# DAC_STM32_Board_v6_-_AD5391.net
KiCad netlist of a schematic drawn in EAGLE
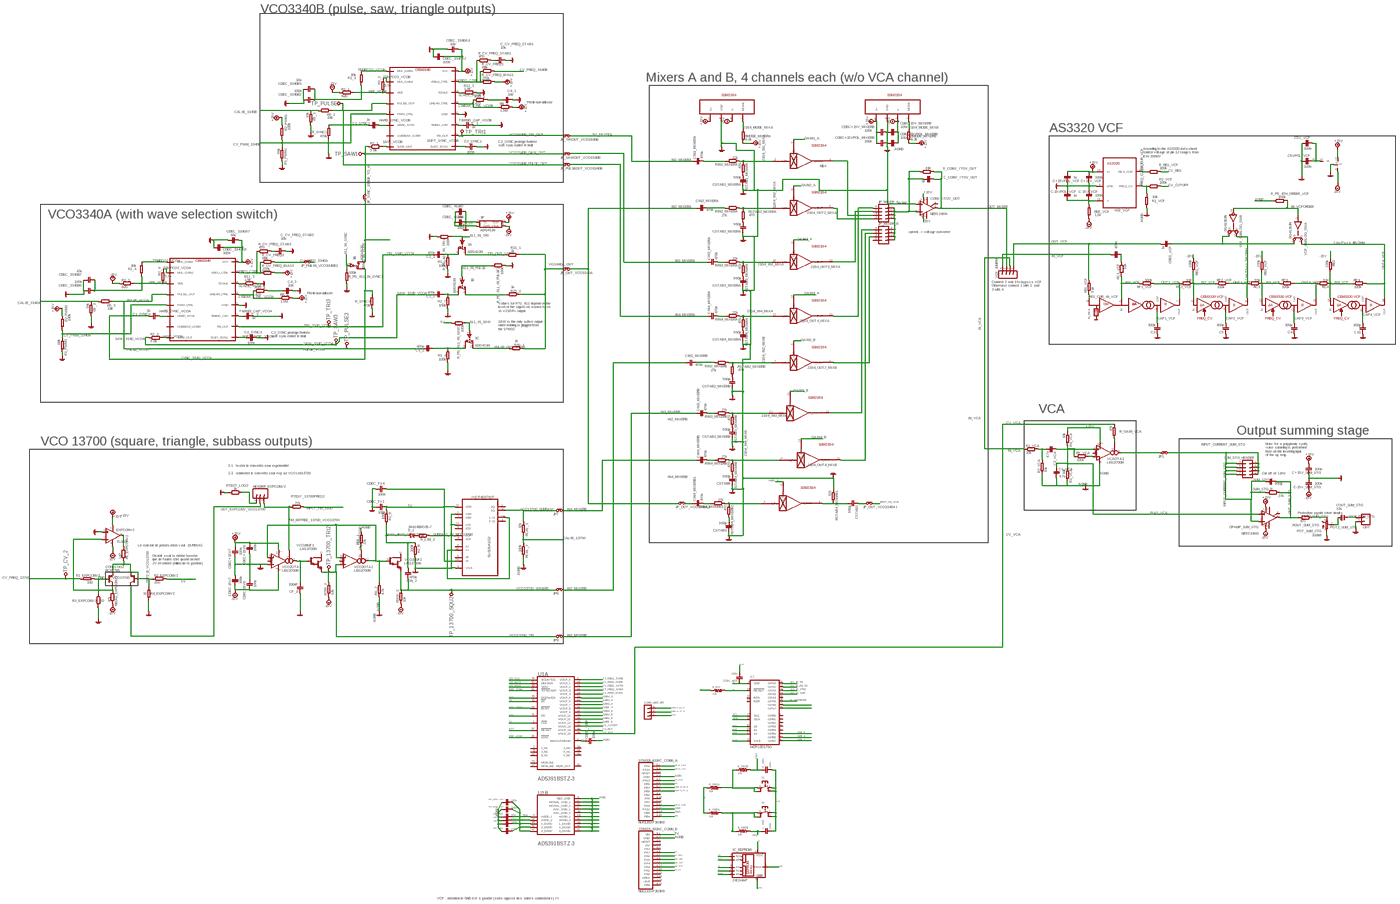
[diagram p0: schematic, sheet 1, overview]
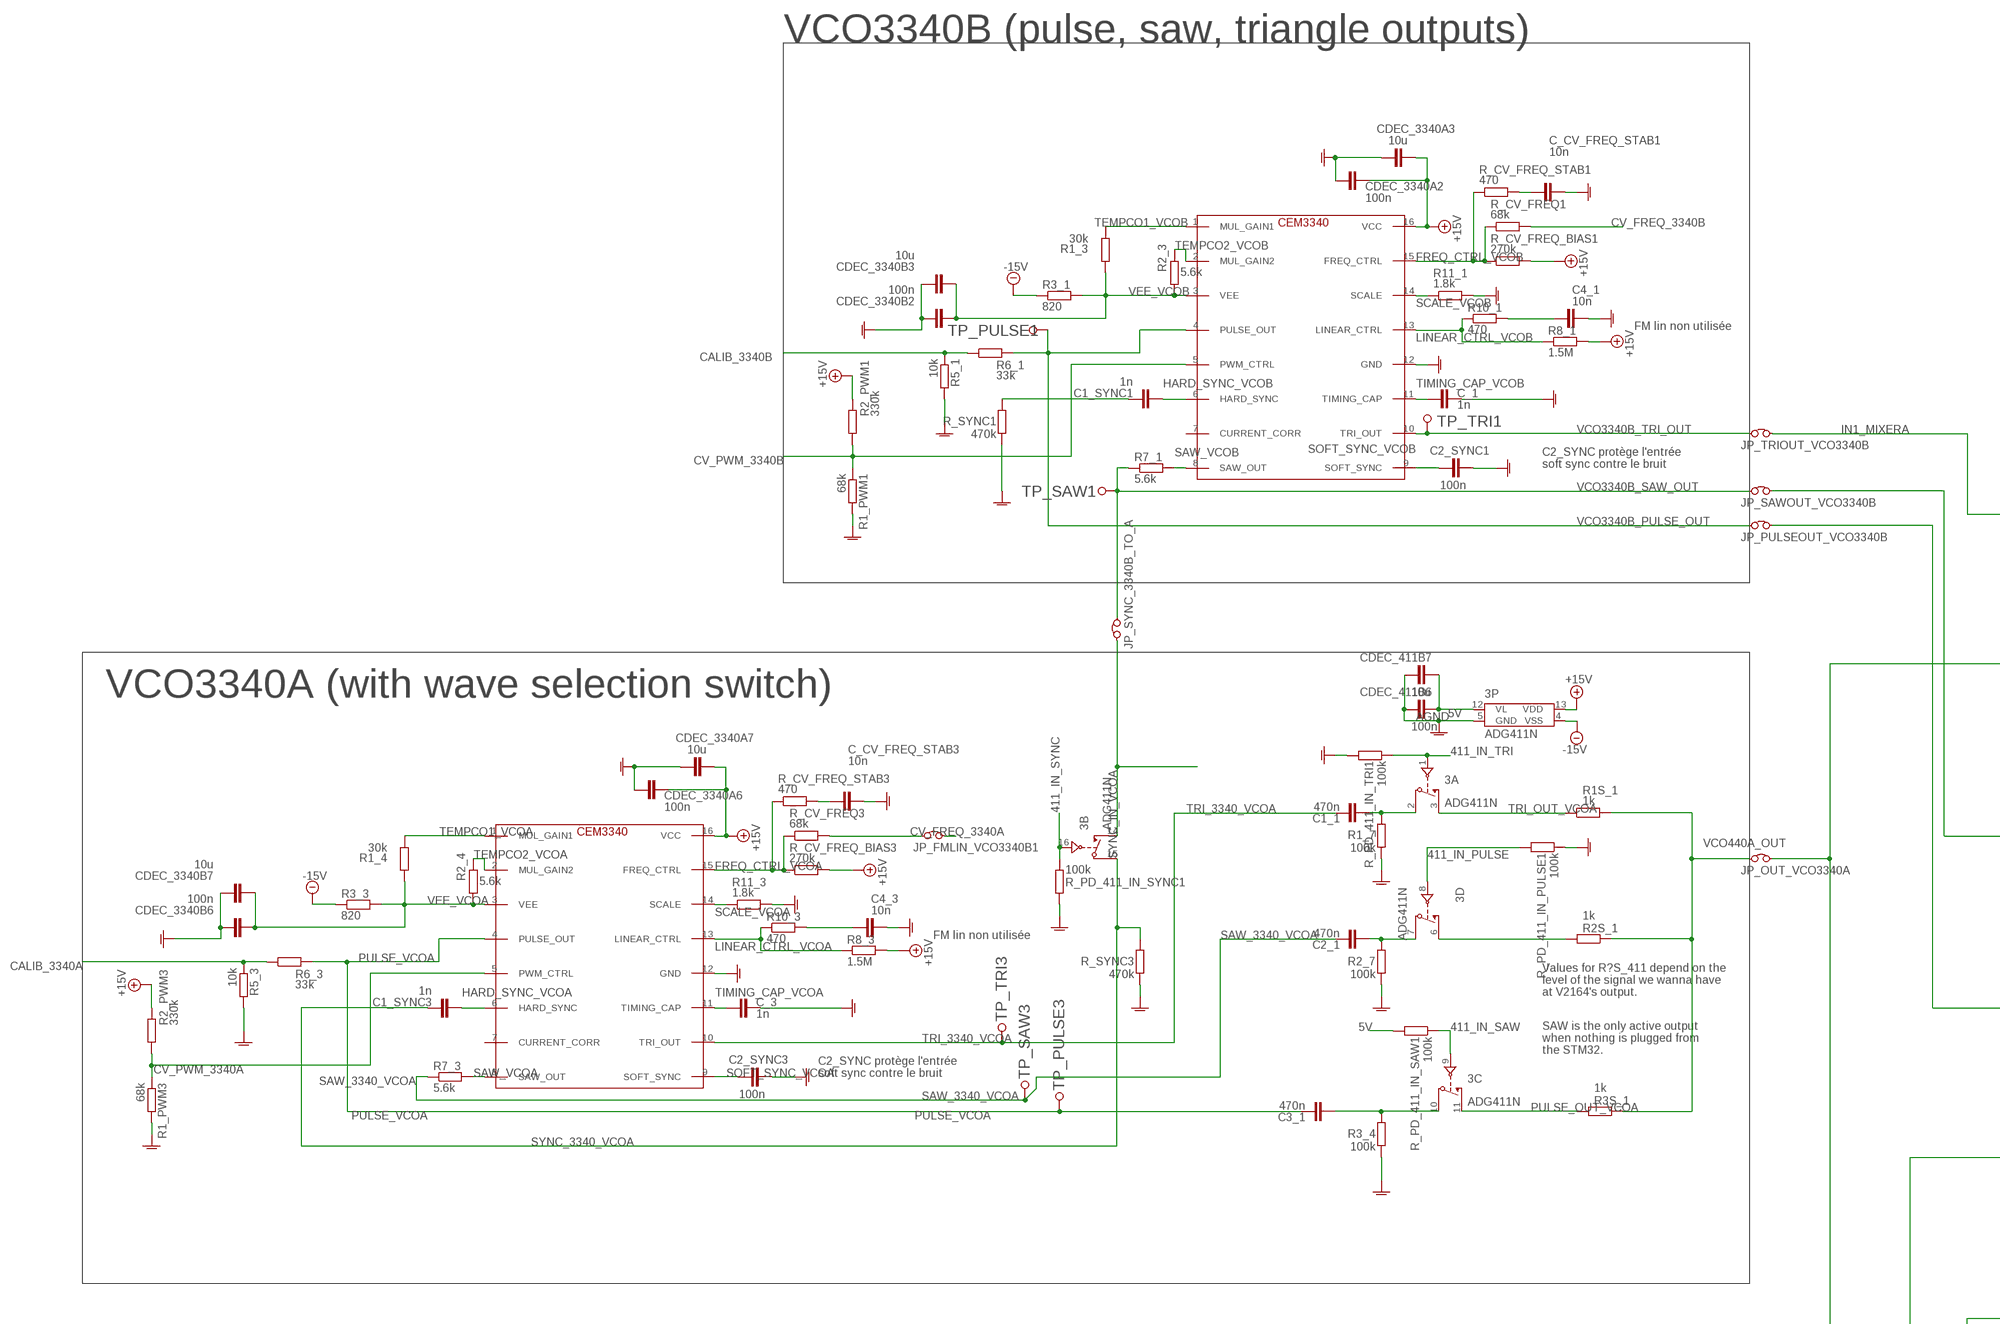
[diagram p1: schematic, sheet 1, part 1 of 5]
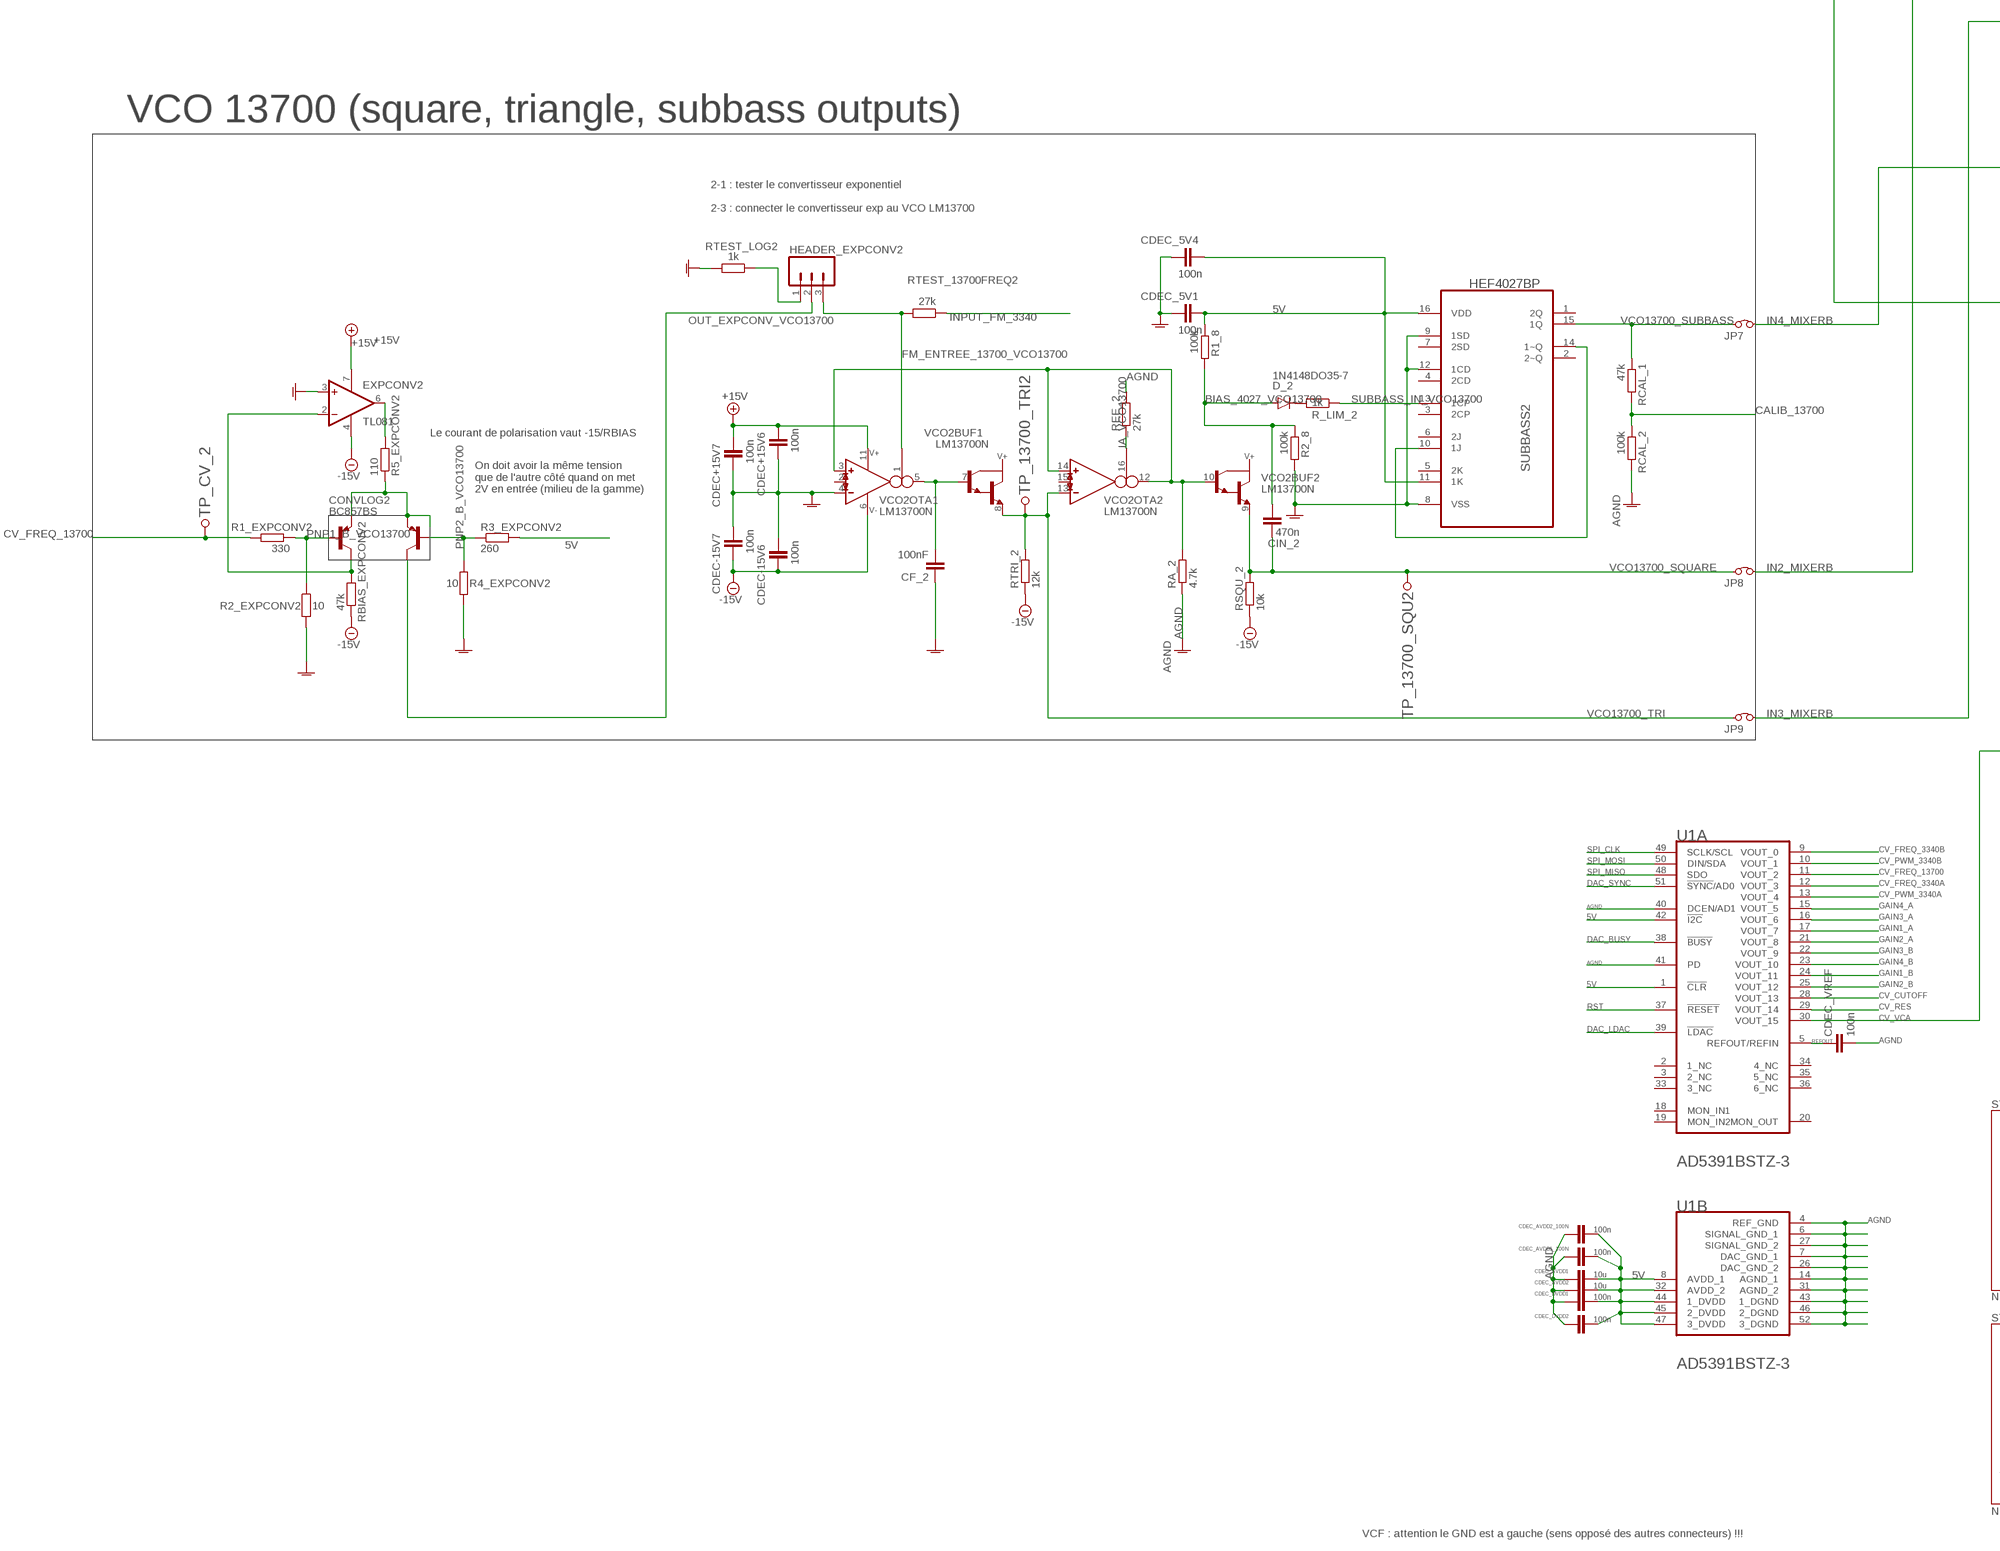
[diagram p2: schematic, sheet 1, part 2 of 5]
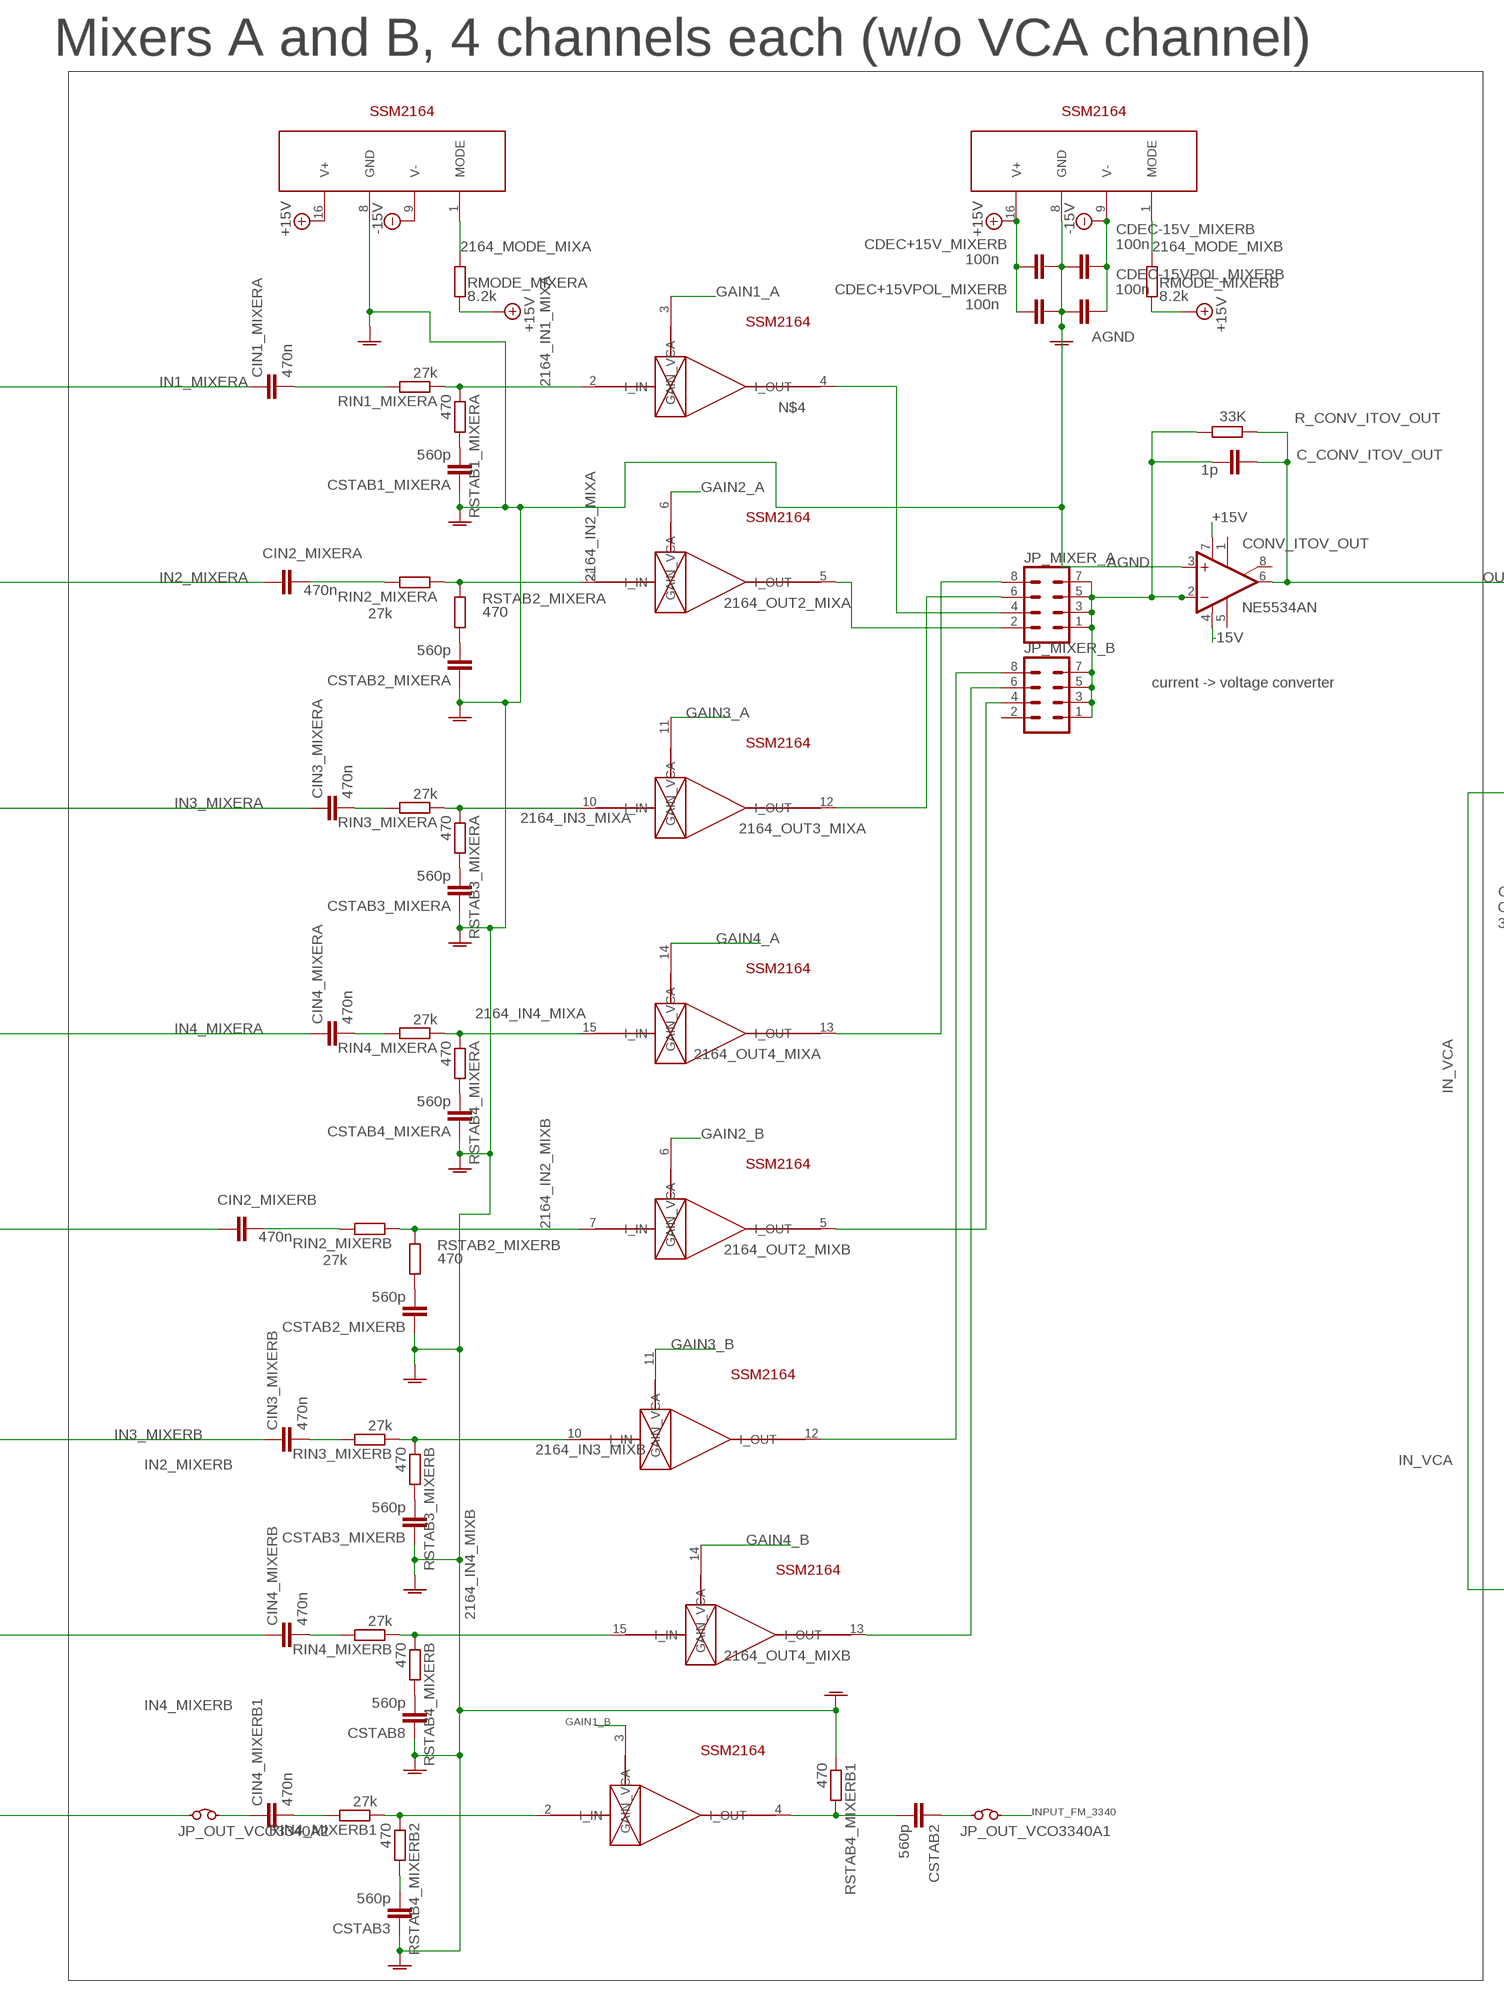
[diagram p3: schematic, sheet 1, part 3 of 5]
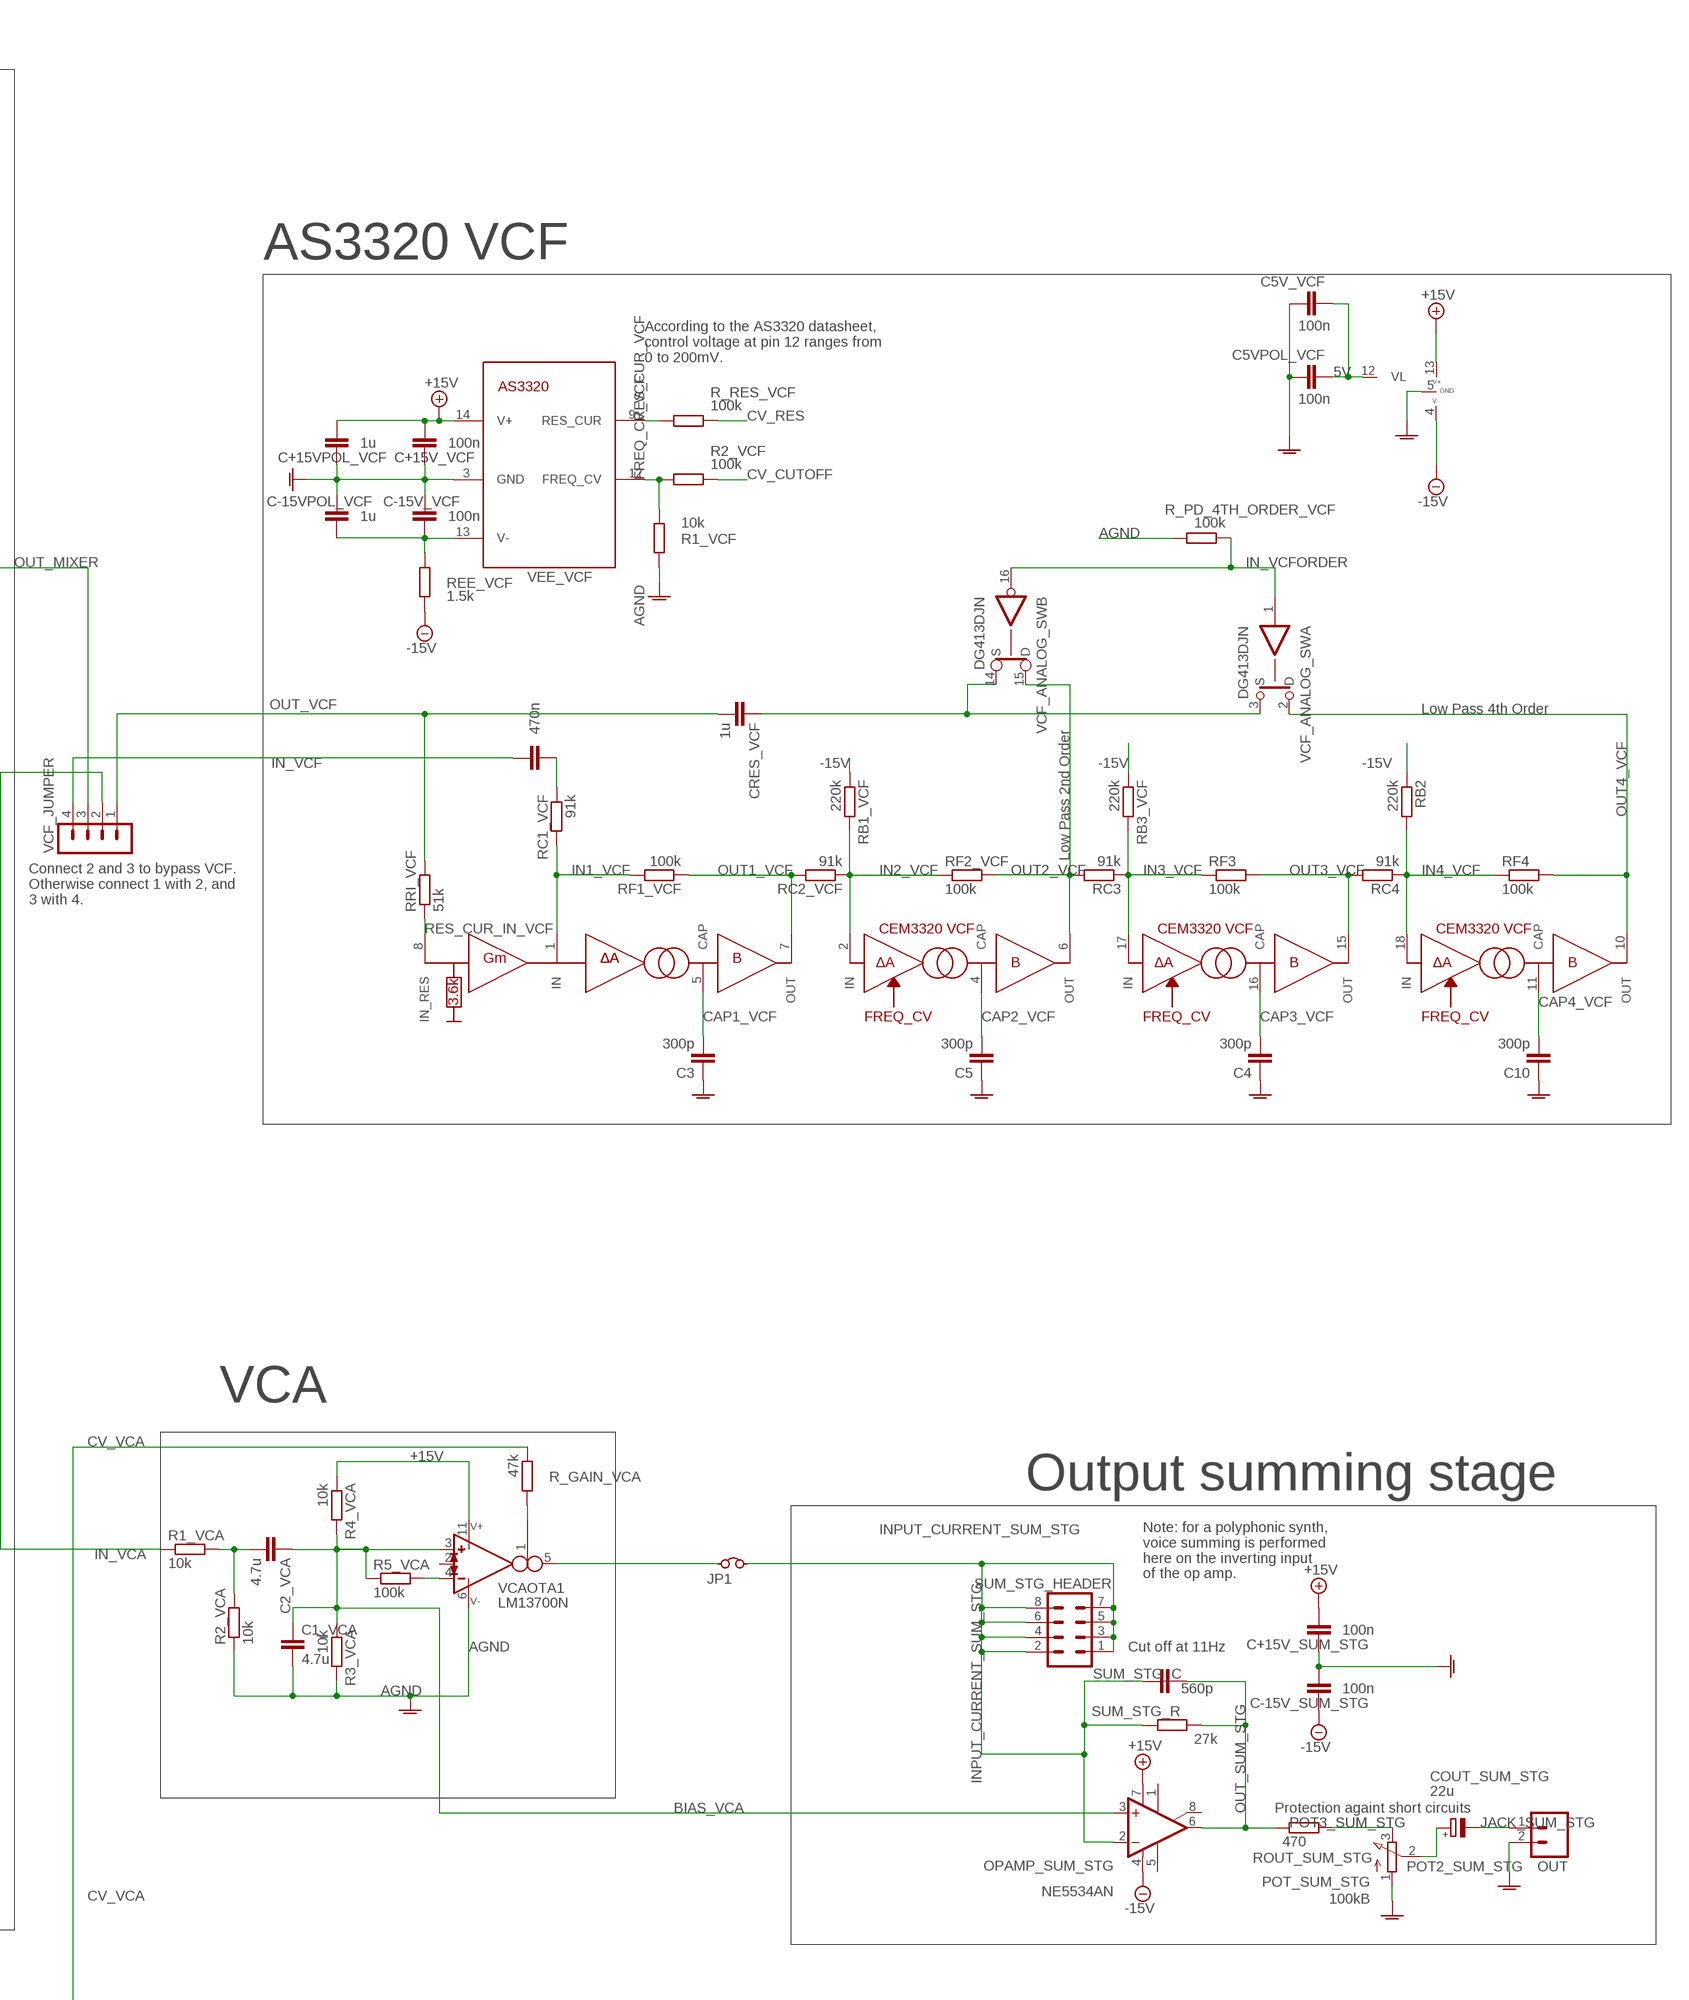
[diagram p4: schematic, sheet 1, part 4 of 5]
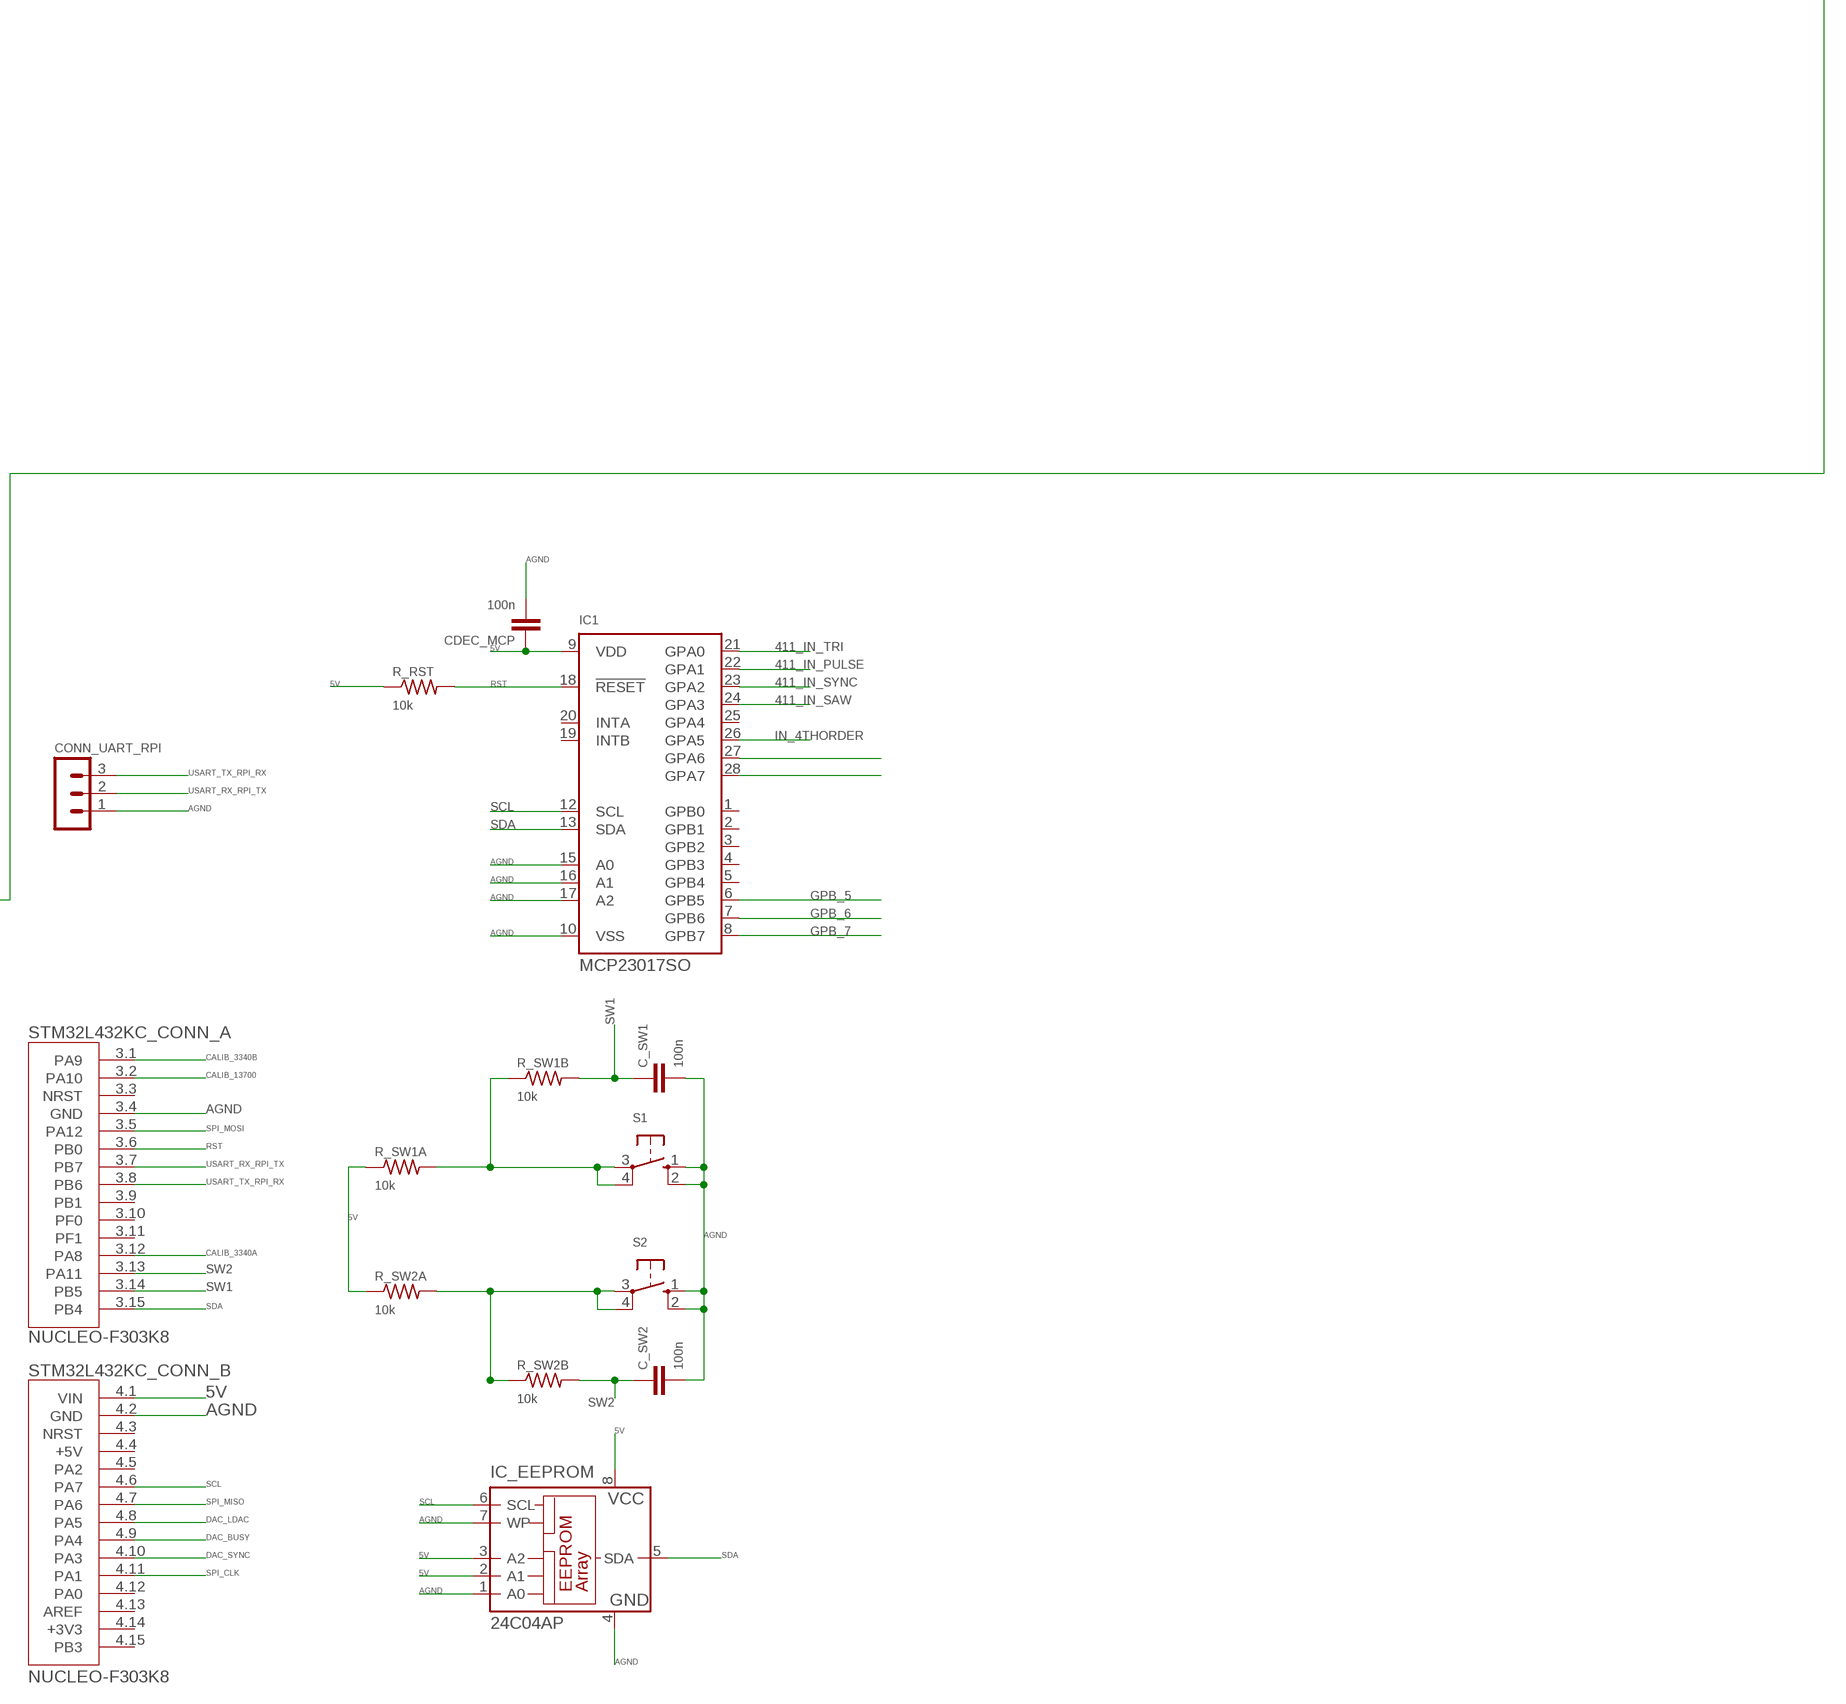
[diagram p5: schematic, sheet 1, part 5 of 5]

(export (version "E")
  (design (tool "Eeschema 10.0.6"))
  (components
    (comp (ref "3")
      (value "ADG411N")
      (footprint "eagle-import:DIL16")
      (fields (field (name "MF") "ALTERA CORPORATION") (field (name "MPN") "ADG411BN"))
      (libsource (lib "eagle-import") (part "ADG411N"))
    )
    (comp (ref "3340A")
      (value "CEM3340")
      (footprint "eagle-import:DIL16")
      (libsource (lib "eagle-import") (part "CEM3340"))
    )
    (comp (ref "3340B")
      (value "CEM3340")
      (footprint "eagle-import:DIL16")
      (libsource (lib "eagle-import") (part "CEM3340"))
    )
    (comp (ref "C+15VPOL_VCF")
      (value "1u")
      (footprint "eagle-import:C075-032X103")
      (libsource (lib "eagle-import") (part "rcl_334_C-EU075-032X103"))
    )
    (comp (ref "C+15V_SUM_STG")
      (value "100n")
      (footprint "eagle-import:C075-032X103")
      (libsource (lib "eagle-import") (part "rcl_334_C-EU075-032X103"))
    )
    (comp (ref "C+15V_VCF")
      (value "100n")
      (footprint "eagle-import:C075-032X103")
      (libsource (lib "eagle-import") (part "rcl_334_C-EU075-032X103"))
    )
    (comp (ref "C-15VPOL_VCF")
      (value "1u")
      (footprint "eagle-import:C075-032X103")
      (libsource (lib "eagle-import") (part "rcl_334_C-EU075-032X103"))
    )
    (comp (ref "C-15V_SUM_STG")
      (value "100n")
      (footprint "eagle-import:C075-032X103")
      (libsource (lib "eagle-import") (part "rcl_334_C-EU075-032X103"))
    )
    (comp (ref "C-15V_VCF")
      (value "100n")
      (footprint "eagle-import:C075-032X103")
      (libsource (lib "eagle-import") (part "rcl_334_C-EU075-032X103"))
    )
    (comp (ref "C1_1")
      (value "470n")
      (footprint "eagle-import:C075-032X103")
      (libsource (lib "eagle-import") (part "rcl_334_C-EU075-032X103"))
    )
    (comp (ref "C1_SYNC1")
      (value "1n")
      (footprint "eagle-import:C075-032X103")
      (libsource (lib "eagle-import") (part "rcl_334_C-EU075-032X103"))
    )
    (comp (ref "C1_SYNC3")
      (value "1n")
      (footprint "eagle-import:C075-032X103")
      (libsource (lib "eagle-import") (part "rcl_334_C-EU075-032X103"))
    )
    (comp (ref "C1_VCA")
      (value "4.7u")
      (footprint "eagle-import:C050-030X075")
      (libsource (lib "eagle-import") (part "rcl_334_C-EU050-030X075"))
    )
    (comp (ref "C2_1")
      (value "470n")
      (footprint "eagle-import:C075-032X103")
      (libsource (lib "eagle-import") (part "rcl_334_C-EU075-032X103"))
    )
    (comp (ref "C2_SYNC1")
      (value "100n")
      (footprint "eagle-import:C075-032X103")
      (libsource (lib "eagle-import") (part "rcl_334_C-EU075-032X103"))
    )
    (comp (ref "C2_SYNC3")
      (value "100n")
      (footprint "eagle-import:C050-025X075")
      (libsource (lib "eagle-import") (part "rcl_334_C-EU050-025X075"))
    )
    (comp (ref "C2_VCA")
      (value "4.7u")
      (footprint "eagle-import:C050-030X075")
      (libsource (lib "eagle-import") (part "rcl_334_C-EU050-030X075"))
    )
    (comp (ref "C3")
      (value "300p")
      (footprint "eagle-import:C075-032X103")
      (libsource (lib "eagle-import") (part "rcl_334_C-EU075-032X103"))
    )
    (comp (ref "C3_1")
      (value "470n")
      (footprint "eagle-import:C102-043X133")
      (libsource (lib "eagle-import") (part "rcl_334_C-EU102-043X133"))
    )
    (comp (ref "C4")
      (value "300p")
      (footprint "eagle-import:C075-032X103")
      (libsource (lib "eagle-import") (part "rcl_334_C-EU075-032X103"))
    )
    (comp (ref "C4_1")
      (value "10n")
      (footprint "eagle-import:C050-025X075")
      (libsource (lib "eagle-import") (part "rcl_334_C-EU050-025X075"))
    )
    (comp (ref "C4_3")
      (value "10n")
      (footprint "eagle-import:C050-025X075")
      (libsource (lib "eagle-import") (part "rcl_334_C-EU050-025X075"))
    )
    (comp (ref "C5")
      (value "300p")
      (footprint "eagle-import:C075-032X103")
      (libsource (lib "eagle-import") (part "rcl_334_C-EU075-032X103"))
    )
    (comp (ref "C5VPOL_VCF")
      (value "100n")
      (footprint "eagle-import:C075-032X103")
      (libsource (lib "eagle-import") (part "rcl_334_C-EU075-032X103"))
    )
    (comp (ref "C5V_VCF")
      (value "100n")
      (footprint "eagle-import:C075-032X103")
      (libsource (lib "eagle-import") (part "rcl_334_C-EU075-032X103"))
    )
    (comp (ref "C10")
      (value "300p")
      (footprint "eagle-import:C075-032X103")
      (libsource (lib "eagle-import") (part "rcl_334_C-EU075-032X103"))
    )
    (comp (ref "CDEC+15V6")
      (value "100n")
      (footprint "eagle-import:C075-032X103")
      (libsource (lib "eagle-import") (part "rcl_334_C-EU075-032X103"))
    )
    (comp (ref "CDEC+15V7")
      (value "100n")
      (footprint "eagle-import:C050-025X075")
      (libsource (lib "eagle-import") (part "rcl_334_C-EU050-025X075"))
    )
    (comp (ref "CDEC+15VPOL_MIXERB")
      (value "100n")
      (footprint "eagle-import:C075-032X103")
      (libsource (lib "eagle-import") (part "rcl_334_C-EU075-032X103"))
    )
    (comp (ref "CDEC+15V_MIXERB")
      (value "100n")
      (footprint "eagle-import:C050-030X075")
      (libsource (lib "eagle-import") (part "rcl_334_C-EU050-030X075"))
    )
    (comp (ref "CDEC-15V6")
      (value "100n")
      (footprint "eagle-import:C050-025X075")
      (libsource (lib "eagle-import") (part "rcl_334_C-EU050-025X075"))
    )
    (comp (ref "CDEC-15V7")
      (value "100n")
      (footprint "eagle-import:C075-032X103")
      (libsource (lib "eagle-import") (part "rcl_334_C-EU075-032X103"))
    )
    (comp (ref "CDEC-15VPOL_MIXERB")
      (value "100n")
      (footprint "eagle-import:C050-030X075")
      (libsource (lib "eagle-import") (part "rcl_334_C-EU050-030X075"))
    )
    (comp (ref "CDEC-15V_MIXERB")
      (value "100n")
      (footprint "eagle-import:C050-030X075")
      (libsource (lib "eagle-import") (part "rcl_334_C-EU050-030X075"))
    )
    (comp (ref "CDEC_5V1")
      (value "100n")
      (footprint "eagle-import:C050-025X075")
      (libsource (lib "eagle-import") (part "rcl_334_C-EU050-025X075"))
    )
    (comp (ref "CDEC_5V4")
      (value "100n")
      (footprint "eagle-import:C050-025X075")
      (libsource (lib "eagle-import") (part "rcl_334_C-EU050-025X075"))
    )
    (comp (ref "CDEC_411B6")
      (value "100n")
      (footprint "eagle-import:C050-025X075")
      (libsource (lib "eagle-import") (part "rcl_334_C-EU050-025X075"))
    )
    (comp (ref "CDEC_411B7")
      (value "10u")
      (footprint "eagle-import:C050-025X075")
      (libsource (lib "eagle-import") (part "rcl_334_C-EU050-025X075"))
    )
    (comp (ref "CDEC_3340A2")
      (value "100n")
      (footprint "eagle-import:C050-025X075")
      (libsource (lib "eagle-import") (part "rcl_334_C-EU050-025X075"))
    )
    (comp (ref "CDEC_3340A3")
      (value "10u")
      (footprint "eagle-import:C075-032X103")
      (libsource (lib "eagle-import") (part "rcl_334_C-EU075-032X103"))
    )
    (comp (ref "CDEC_3340A6")
      (value "100n")
      (footprint "eagle-import:C050-025X075")
      (libsource (lib "eagle-import") (part "rcl_334_C-EU050-025X075"))
    )
    (comp (ref "CDEC_3340A7")
      (value "10u")
      (footprint "eagle-import:C050-025X075")
      (libsource (lib "eagle-import") (part "rcl_334_C-EU050-025X075"))
    )
    (comp (ref "CDEC_3340B2")
      (value "100n")
      (footprint "eagle-import:C050-025X075")
      (libsource (lib "eagle-import") (part "rcl_334_C-EU050-025X075"))
    )
    (comp (ref "CDEC_3340B3")
      (value "10u")
      (footprint "eagle-import:C050-025X075")
      (libsource (lib "eagle-import") (part "rcl_334_C-EU050-025X075"))
    )
    (comp (ref "CDEC_3340B6")
      (value "100n")
      (footprint "eagle-import:C050-025X075")
      (libsource (lib "eagle-import") (part "rcl_334_C-EU050-025X075"))
    )
    (comp (ref "CDEC_3340B7")
      (value "10u")
      (footprint "eagle-import:C050-025X075")
      (libsource (lib "eagle-import") (part "rcl_334_C-EU050-025X075"))
    )
    (comp (ref "CDEC_AVDD1")
      (value "10u")
      (footprint "eagle-import:C050-030X075")
      (libsource (lib "eagle-import") (part "C-EU050-030X075"))
    )
    (comp (ref "CDEC_AVDD1_100N")
      (value "100n")
      (footprint "eagle-import:C050-030X075")
      (libsource (lib "eagle-import") (part "C-EU050-030X075"))
    )
    (comp (ref "CDEC_AVDD2")
      (value "10u")
      (footprint "eagle-import:C050-030X075")
      (libsource (lib "eagle-import") (part "C-EU050-030X075"))
    )
    (comp (ref "CDEC_AVDD2_100N")
      (value "100n")
      (footprint "eagle-import:C050-030X075")
      (libsource (lib "eagle-import") (part "C-EU050-030X075"))
    )
    (comp (ref "CDEC_DVDD1")
      (value "100n")
      (footprint "eagle-import:C075-032X103")
      (libsource (lib "eagle-import") (part "C-EU075-032X103"))
    )
    (comp (ref "CDEC_DVDD2")
      (value "100n")
      (footprint "eagle-import:C050-030X075")
      (libsource (lib "eagle-import") (part "C-EU050-030X075"))
    )
    (comp (ref "CDEC_MCP")
      (value "100n")
      (footprint "eagle-import:C075-032X103")
      (libsource (lib "eagle-import") (part "C-EU075-032X103"))
    )
    (comp (ref "CDEC_VREF")
      (value "100n")
      (footprint "eagle-import:C050-030X075")
      (libsource (lib "eagle-import") (part "C-EU050-030X075"))
    )
    (comp (ref "CF_2")
      (value "100nF")
      (footprint "eagle-import:C050-025X075")
      (libsource (lib "eagle-import") (part "rcl_334_C-EU050-025X075"))
    )
    (comp (ref "CIN1_MIXERA")
      (value "470n")
      (footprint "eagle-import:C050-030X075")
      (fields (field (name "C3") "0.47 micro"))
      (libsource (lib "eagle-import") (part "rcl_334_C-EU050-030X075"))
    )
    (comp (ref "CIN2_MIXERA")
      (value "470n")
      (footprint "eagle-import:C050-030X075")
      (fields (field (name "C3") "0.47 micro"))
      (libsource (lib "eagle-import") (part "rcl_334_C-EU050-030X075"))
    )
    (comp (ref "CIN2_MIXERB")
      (value "470n")
      (footprint "eagle-import:C050-030X075")
      (fields (field (name "C3") "0.47 micro"))
      (libsource (lib "eagle-import") (part "rcl_334_C-EU050-030X075"))
    )
    (comp (ref "CIN3_MIXERA")
      (value "470n")
      (footprint "eagle-import:C050-030X075")
      (fields (field (name "C3") "0.47 micro"))
      (libsource (lib "eagle-import") (part "rcl_334_C-EU050-030X075"))
    )
    (comp (ref "CIN3_MIXERB")
      (value "470n")
      (footprint "eagle-import:C050-030X075")
      (fields (field (name "C3") "0.47 micro"))
      (libsource (lib "eagle-import") (part "rcl_334_C-EU050-030X075"))
    )
    (comp (ref "CIN4_MIXERA")
      (value "470n")
      (footprint "eagle-import:C050-030X075")
      (fields (field (name "C3") "0.47 micro"))
      (libsource (lib "eagle-import") (part "rcl_334_C-EU050-030X075"))
    )
    (comp (ref "CIN4_MIXERB")
      (value "470n")
      (footprint "eagle-import:C050-030X075")
      (fields (field (name "C3") "0.47 micro"))
      (libsource (lib "eagle-import") (part "rcl_334_C-EU050-030X075"))
    )
    (comp (ref "CIN4_MIXERB1")
      (value "470n")
      (footprint "eagle-import:C050-030X075")
      (fields (field (name "C3") "0.47 micro"))
      (libsource (lib "eagle-import") (part "rcl_334_C-EU050-030X075"))
    )
    (comp (ref "CIN_2")
      (value "470n")
      (footprint "eagle-import:C050-025X075")
      (libsource (lib "eagle-import") (part "rcl_334_C-EU050-025X075"))
    )
    (comp (ref "CONN_UART_RPI")
      (value "MA03-1")
      (footprint "eagle-import:MA03-1")
      (libsource (lib "eagle-import") (part "MA03-1"))
    )
    (comp (ref "CONVLOG2")
      (value "BC857BS")
      (footprint "eagle-import:DIL06")
      (libsource (lib "eagle-import") (part "BC857BS"))
    )
    (comp (ref "CONV_ITOV_OUT")
      (value "NE5534AN")
      (footprint "eagle-import:DIL08")
      (libsource (lib "eagle-import") (part "linear_262_NE5534NA"))
    )
    (comp (ref "COUT_SUM_STG")
      (value "22u")
      (footprint "eagle-import:B45181A")
      (libsource (lib "eagle-import") (part "CPOL-EUB45181A"))
    )
    (comp (ref "CRES_VCF")
      (value "1u")
      (footprint "eagle-import:C075-032X103")
      (libsource (lib "eagle-import") (part "rcl_334_C-EU075-032X103"))
    )
    (comp (ref "CSTAB1_MIXERA")
      (value "560p")
      (footprint "eagle-import:C050-030X075")
      (libsource (lib "eagle-import") (part "rcl_334_C-EU050-030X075"))
    )
    (comp (ref "CSTAB2")
      (value "560p")
      (footprint "eagle-import:C050-030X075")
      (libsource (lib "eagle-import") (part "rcl_334_C-EU050-030X075"))
    )
    (comp (ref "CSTAB2_MIXERA")
      (value "560p")
      (footprint "eagle-import:C050-030X075")
      (libsource (lib "eagle-import") (part "rcl_334_C-EU050-030X075"))
    )
    (comp (ref "CSTAB2_MIXERB")
      (value "560p")
      (footprint "eagle-import:C050-030X075")
      (libsource (lib "eagle-import") (part "rcl_334_C-EU050-030X075"))
    )
    (comp (ref "CSTAB3")
      (value "560p")
      (footprint "eagle-import:C050-030X075")
      (libsource (lib "eagle-import") (part "rcl_334_C-EU050-030X075"))
    )
    (comp (ref "CSTAB3_MIXERA")
      (value "560p")
      (footprint "eagle-import:C050-030X075")
      (libsource (lib "eagle-import") (part "rcl_334_C-EU050-030X075"))
    )
    (comp (ref "CSTAB3_MIXERB")
      (value "560p")
      (footprint "eagle-import:C050-030X075")
      (libsource (lib "eagle-import") (part "rcl_334_C-EU050-030X075"))
    )
    (comp (ref "CSTAB4_MIXERA")
      (value "560p")
      (footprint "eagle-import:C050-030X075")
      (libsource (lib "eagle-import") (part "rcl_334_C-EU050-030X075"))
    )
    (comp (ref "CSTAB8")
      (value "560p")
      (footprint "eagle-import:C050-030X075")
      (libsource (lib "eagle-import") (part "rcl_334_C-EU050-030X075"))
    )
    (comp (ref "C_1")
      (value "1n")
      (footprint "eagle-import:C050-025X075")
      (libsource (lib "eagle-import") (part "rcl_334_C-EU050-025X075"))
    )
    (comp (ref "C_3")
      (value "1n")
      (footprint "eagle-import:C050-025X075")
      (libsource (lib "eagle-import") (part "rcl_334_C-EU050-025X075"))
    )
    (comp (ref "C_CONV_ITOV_OUT")
      (value "1p")
      (footprint "eagle-import:C050-030X075")
      (fields (field (name "C3") "0.47 micro"))
      (libsource (lib "eagle-import") (part "rcl_334_C-EU050-030X075"))
    )
    (comp (ref "C_CV_FREQ_STAB1")
      (value "10n")
      (footprint "eagle-import:C075-032X103")
      (libsource (lib "eagle-import") (part "rcl_334_C-EU075-032X103"))
    )
    (comp (ref "C_CV_FREQ_STAB3")
      (value "10n")
      (footprint "eagle-import:C075-032X103")
      (libsource (lib "eagle-import") (part "rcl_334_C-EU075-032X103"))
    )
    (comp (ref "C_IN2")
      (value "470n")
      (footprint "eagle-import:C050-025X075")
      (libsource (lib "eagle-import") (part "rcl_334_C-EU050-025X075"))
    )
    (comp (ref "C_SW1")
      (value "100n")
      (footprint "eagle-import:C050-030X075")
      (libsource (lib "eagle-import") (part "C-EU050-030X075"))
    )
    (comp (ref "C_SW2")
      (value "100n")
      (footprint "eagle-import:C050-030X075")
      (libsource (lib "eagle-import") (part "C-EU050-030X075"))
    )
    (comp (ref "D_2")
      (value "1N4148DO35-7")
      (footprint "eagle-import:DO35-7")
      (libsource (lib "eagle-import") (part "1N4148DO35-7"))
    )
    (comp (ref "EXPCONV2")
      (value "TL081")
      (footprint "eagle-import:DIL08")
      (libsource (lib "eagle-import") (part "1AMP_P7+4N"))
    )
    (comp (ref "HEADER_EXPCONV2")
      (value "M03")
      (footprint "eagle-import:03P")
      (libsource (lib "eagle-import") (part "M03"))
    )
    (comp (ref "IC1")
      (value "MCP23017SO")
      (footprint "eagle-import:SO28W")
      (fields (field (name "MF") "MICROCHIP") (field (name "MPN") "MCP23017-E/SO"))
      (libsource (lib "eagle-import") (part "MCP23017SO"))
    )
    (comp (ref "IC_EEPROM")
      (value "24C04AP")
      (footprint "eagle-import:DIL8")
      (fields (field (name "MPN") "AT24C04B-PU"))
      (libsource (lib "eagle-import") (part "24CP04A"))
    )
    (comp (ref "JP1")
      (value "JUMPER")
      (footprint "eagle-import:HDR2X1")
      (libsource (lib "eagle-import") (part "JUMPER"))
    )
    (comp (ref "JP7")
      (value "JUMPER")
      (footprint "eagle-import:HDR2X1")
      (libsource (lib "eagle-import") (part "JUMPER"))
    )
    (comp (ref "JP8")
      (value "JUMPER")
      (footprint "eagle-import:HDR2X1")
      (libsource (lib "eagle-import") (part "JUMPER"))
    )
    (comp (ref "JP9")
      (value "JUMPER")
      (footprint "eagle-import:HDR2X1")
      (libsource (lib "eagle-import") (part "JUMPER"))
    )
    (comp (ref "JP_FMLIN_VCO3340B1")
      (value "JUMPER")
      (footprint "eagle-import:HDR2X1")
      (libsource (lib "eagle-import") (part "JUMPER"))
    )
    (comp (ref "JP_MIXER_A")
      (value "MA04-2")
      (footprint "eagle-import:MA04-2")
      (libsource (lib "eagle-import") (part "MA04-2"))
    )
    (comp (ref "JP_MIXER_B")
      (value "MA04-2")
      (footprint "eagle-import:MA04-2")
      (libsource (lib "eagle-import") (part "MA04-2"))
    )
    (comp (ref "JP_OUT_VCO3340A")
      (value "JUMPER")
      (footprint "eagle-import:HDR2X1")
      (libsource (lib "eagle-import") (part "JUMPER"))
    )
    (comp (ref "JP_OUT_VCO3340A1")
      (value "JUMPER")
      (footprint "eagle-import:HDR2X1")
      (libsource (lib "eagle-import") (part "JUMPER"))
    )
    (comp (ref "JP_OUT_VCO3340A2")
      (value "JUMPER")
      (footprint "eagle-import:HDR2X1")
      (libsource (lib "eagle-import") (part "JUMPER"))
    )
    (comp (ref "JP_PULSEOUT_VCO3340B")
      (value "JUMPER")
      (footprint "eagle-import:HDR2X1")
      (libsource (lib "eagle-import") (part "JUMPER"))
    )
    (comp (ref "JP_SAWOUT_VCO3340B")
      (value "JUMPER")
      (footprint "eagle-import:HDR2X1")
      (libsource (lib "eagle-import") (part "JUMPER"))
    )
    (comp (ref "JP_SYNC_3340B_TO_A")
      (value "JUMPER")
      (footprint "eagle-import:HDR2X1")
      (libsource (lib "eagle-import") (part "JUMPER"))
    )
    (comp (ref "JP_TRIOUT_VCO3340B")
      (value "JUMPER")
      (footprint "eagle-import:HDR2X1")
      (libsource (lib "eagle-import") (part "JUMPER"))
    )
    (comp (ref "MIXER_A")
      (value "SSM2164_MULTI")
      (footprint "eagle-import:DIL16")
      (libsource (lib "eagle-import") (part "SSM2164_MULTI"))
    )
    (comp (ref "MIXER_B")
      (value "SSM2164_MULTI")
      (footprint "eagle-import:DIL16")
      (libsource (lib "eagle-import") (part "SSM2164_MULTI"))
    )
    (comp (ref "OPAMP_SUM_STG")
      (value "NE5534AN")
      (footprint "eagle-import:DIL08")
      (libsource (lib "eagle-import") (part "NE5534NA"))
    )
    (comp (ref "OUT")
      (value "MA02")
      (footprint "eagle-import:02PA")
      (libsource (lib "eagle-import") (part "MA02"))
    )
    (comp (ref "POT_SUM_STG")
      (value "100kB")
      (footprint "eagle-import:3RP_1610N")
      (libsource (lib "eagle-import") (part "3RP/1610N"))
    )
    (comp (ref "R1S_1")
      (value "1k")
      (footprint "eagle-import:0204_7")
      (libsource (lib "eagle-import") (part "R-EU_0204/7"))
    )
    (comp (ref "R1_3")
      (value "30k")
      (footprint "eagle-import:0204_7")
      (libsource (lib "eagle-import") (part "R-EU_0204/7"))
    )
    (comp (ref "R1_4")
      (value "30k")
      (footprint "eagle-import:0204_7")
      (libsource (lib "eagle-import") (part "R-EU_0204/7"))
    )
    (comp (ref "R1_7")
      (value "100k")
      (footprint "eagle-import:0204_7")
      (libsource (lib "eagle-import") (part "R-EU_0204/7"))
    )
    (comp (ref "R1_8")
      (value "100k")
      (footprint "eagle-import:0204_7")
      (libsource (lib "eagle-import") (part "R-EU_0204/7"))
    )
    (comp (ref "R1_EXPCONV2")
      (value "330")
      (footprint "eagle-import:0204_7")
      (libsource (lib "eagle-import") (part "R-EU_0204/7"))
    )
    (comp (ref "R1_PWM1")
      (value "68k")
      (footprint "eagle-import:0204_7")
      (libsource (lib "eagle-import") (part "R-EU_0204/7"))
    )
    (comp (ref "R1_PWM3")
      (value "68k")
      (footprint "eagle-import:0207_10")
      (libsource (lib "eagle-import") (part "R-EU_0207/10"))
    )
    (comp (ref "R1_VCA")
      (value "10k")
      (footprint "eagle-import:0204_7")
      (libsource (lib "eagle-import") (part "R-EU_0204/7"))
    )
    (comp (ref "R1_VCF")
      (value "10k")
      (footprint "eagle-import:0204_7")
      (libsource (lib "eagle-import") (part "R-EU_0204/7"))
    )
    (comp (ref "R2S_1")
      (value "1k")
      (footprint "eagle-import:0204_7")
      (libsource (lib "eagle-import") (part "R-EU_0204/7"))
    )
    (comp (ref "R2_3")
      (value "5.6k")
      (footprint "eagle-import:0204_7")
      (libsource (lib "eagle-import") (part "R-EU_0204/7"))
    )
    (comp (ref "R2_4")
      (value "5.6k")
      (footprint "eagle-import:0204_7")
      (libsource (lib "eagle-import") (part "R-EU_0204/7"))
    )
    (comp (ref "R2_7")
      (value "100k")
      (footprint "eagle-import:0207_10")
      (libsource (lib "eagle-import") (part "R-EU_0207/10"))
    )
    (comp (ref "R2_8")
      (value "100k")
      (footprint "eagle-import:0204_7")
      (libsource (lib "eagle-import") (part "R-EU_0204/7"))
    )
    (comp (ref "R2_EXPCONV2")
      (value "10")
      (footprint "eagle-import:0204_7")
      (libsource (lib "eagle-import") (part "R-EU_0204/7"))
    )
    (comp (ref "R2_PWM1")
      (value "330k")
      (footprint "eagle-import:0204_7")
      (libsource (lib "eagle-import") (part "R-EU_0204/7"))
    )
    (comp (ref "R2_PWM3")
      (value "330k")
      (footprint "eagle-import:0204_7")
      (libsource (lib "eagle-import") (part "R-EU_0204/7"))
    )
    (comp (ref "R2_VCA")
      (value "10k")
      (footprint "eagle-import:0204_7")
      (libsource (lib "eagle-import") (part "R-EU_0204/7"))
    )
    (comp (ref "R2_VCF")
      (value "100k")
      (footprint "eagle-import:0204_7")
      (libsource (lib "eagle-import") (part "R-EU_0204/7"))
    )
    (comp (ref "R3S_1")
      (value "1k")
      (footprint "eagle-import:0207_10")
      (libsource (lib "eagle-import") (part "R-EU_0207/10"))
    )
    (comp (ref "R3_1")
      (value "820")
      (footprint "eagle-import:0204_7")
      (libsource (lib "eagle-import") (part "R-EU_0204/7"))
    )
    (comp (ref "R3_3")
      (value "820")
      (footprint "eagle-import:0204_7")
      (libsource (lib "eagle-import") (part "R-EU_0204/7"))
    )
    (comp (ref "R3_4")
      (value "100k")
      (footprint "eagle-import:0207_10")
      (libsource (lib "eagle-import") (part "R-EU_0207/10"))
    )
    (comp (ref "R3_EXPCONV2")
      (value "260")
      (footprint "eagle-import:0204_7")
      (libsource (lib "eagle-import") (part "R-EU_0204/7"))
    )
    (comp (ref "R3_VCA")
      (value "10k")
      (footprint "eagle-import:0204_7")
      (libsource (lib "eagle-import") (part "R-EU_0204/7"))
    )
    (comp (ref "R4_EXPCONV2")
      (value "10")
      (footprint "eagle-import:0204_7")
      (libsource (lib "eagle-import") (part "R-EU_0204/7"))
    )
    (comp (ref "R4_VCA")
      (value "10k")
      (footprint "eagle-import:0204_7")
      (libsource (lib "eagle-import") (part "R-EU_0204/7"))
    )
    (comp (ref "R5_1")
      (value "10k")
      (footprint "eagle-import:0204_7")
      (libsource (lib "eagle-import") (part "R-EU_0204/7"))
    )
    (comp (ref "R5_3")
      (value "10k")
      (footprint "eagle-import:0204_7")
      (libsource (lib "eagle-import") (part "R-EU_0204/7"))
    )
    (comp (ref "R5_EXPCONV2")
      (value "110")
      (footprint "eagle-import:0204_7")
      (libsource (lib "eagle-import") (part "R-EU_0204/7"))
    )
    (comp (ref "R5_VCA")
      (value "100k")
      (footprint "eagle-import:0204_7")
      (libsource (lib "eagle-import") (part "R-EU_0204/7"))
    )
    (comp (ref "R6_1")
      (value "33k")
      (footprint "eagle-import:0204_7")
      (libsource (lib "eagle-import") (part "R-EU_0204/7"))
    )
    (comp (ref "R6_3")
      (value "33k")
      (footprint "eagle-import:0204_7")
      (libsource (lib "eagle-import") (part "R-EU_0204/7"))
    )
    (comp (ref "R7_1")
      (value "5.6k")
      (footprint "eagle-import:0207_10")
      (libsource (lib "eagle-import") (part "R-EU_0207/10"))
    )
    (comp (ref "R7_3")
      (value "5.6k")
      (footprint "eagle-import:0207_10")
      (libsource (lib "eagle-import") (part "R-EU_0207/10"))
    )
    (comp (ref "R8_1")
      (value "1.5M")
      (footprint "eagle-import:0204_7")
      (libsource (lib "eagle-import") (part "R-EU_0204/7"))
    )
    (comp (ref "R8_3")
      (value "1.5M")
      (footprint "eagle-import:0204_7")
      (libsource (lib "eagle-import") (part "R-EU_0204/7"))
    )
    (comp (ref "R10_1")
      (value "470")
      (footprint "eagle-import:0204_7")
      (libsource (lib "eagle-import") (part "R-EU_0204/7"))
    )
    (comp (ref "R10_3")
      (value "470")
      (footprint "eagle-import:0204_7")
      (libsource (lib "eagle-import") (part "R-EU_0204/7"))
    )
    (comp (ref "R11_1")
      (value "1.8k")
      (footprint "eagle-import:0204_7")
      (libsource (lib "eagle-import") (part "R-EU_0204/7"))
    )
    (comp (ref "R11_3")
      (value "1.8k")
      (footprint "eagle-import:0204_7")
      (libsource (lib "eagle-import") (part "R-EU_0204/7"))
    )
    (comp (ref "RA_2")
      (value "4.7k")
      (footprint "eagle-import:0204_7")
      (libsource (lib "eagle-import") (part "R-EU_0204/7"))
    )
    (comp (ref "RB1_VCF")
      (value "220k")
      (footprint "eagle-import:0204_7")
      (libsource (lib "eagle-import") (part "R-EU_0204/7"))
    )
    (comp (ref "RB2")
      (value "220k")
      (footprint "eagle-import:0204_7")
      (libsource (lib "eagle-import") (part "R-EU_0204/7"))
    )
    (comp (ref "RB3_VCF")
      (value "220k")
      (footprint "eagle-import:0204_7")
      (libsource (lib "eagle-import") (part "R-EU_0204/7"))
    )
    (comp (ref "RBIAS_EXPCONV2")
      (value "47k")
      (footprint "eagle-import:0204_7")
      (libsource (lib "eagle-import") (part "R-EU_0204/7"))
    )
    (comp (ref "RC1_VCF")
      (value "91k")
      (footprint "eagle-import:0204_7")
      (libsource (lib "eagle-import") (part "R-EU_0204/7"))
    )
    (comp (ref "RC2_VCF")
      (value "91k")
      (footprint "eagle-import:0204_7")
      (libsource (lib "eagle-import") (part "R-EU_0204/7"))
    )
    (comp (ref "RC3")
      (value "91k")
      (footprint "eagle-import:0204_7")
      (libsource (lib "eagle-import") (part "R-EU_0204/7"))
    )
    (comp (ref "RC4")
      (value "91k")
      (footprint "eagle-import:0204_7")
      (libsource (lib "eagle-import") (part "R-EU_0204/7"))
    )
    (comp (ref "RCAL_1")
      (value "47k")
      (footprint "eagle-import:0204_7")
      (libsource (lib "eagle-import") (part "R-EU_0204/7"))
    )
    (comp (ref "RCAL_2")
      (value "100k")
      (footprint "eagle-import:0204_7")
      (libsource (lib "eagle-import") (part "R-EU_0204/7"))
    )
    (comp (ref "REE_2")
      (value "27k")
      (footprint "eagle-import:0204_7")
      (libsource (lib "eagle-import") (part "R-EU_0204/7"))
    )
    (comp (ref "REE_VCF")
      (value "1.5k")
      (footprint "eagle-import:0207_10")
      (libsource (lib "eagle-import") (part "R-EU_0207/10"))
    )
    (comp (ref "RF1_VCF")
      (value "100k")
      (footprint "eagle-import:0207_10")
      (libsource (lib "eagle-import") (part "R-EU_0207/10"))
    )
    (comp (ref "RF2_VCF")
      (value "100k")
      (footprint "eagle-import:0204_7")
      (libsource (lib "eagle-import") (part "R-EU_0204/7"))
    )
    (comp (ref "RF3")
      (value "100k")
      (footprint "eagle-import:0204_7")
      (libsource (lib "eagle-import") (part "R-EU_0204/7"))
    )
    (comp (ref "RF4")
      (value "100k")
      (footprint "eagle-import:0204_7")
      (libsource (lib "eagle-import") (part "R-EU_0204/7"))
    )
    (comp (ref "RIN1_MIXERA")
      (value "27k")
      (footprint "eagle-import:0204_7")
      (libsource (lib "eagle-import") (part "R-EU_0204/7"))
    )
    (comp (ref "RIN2_MIXERA")
      (value "27k")
      (footprint "eagle-import:0207_10")
      (libsource (lib "eagle-import") (part "R-EU_0207/10"))
    )
    (comp (ref "RIN2_MIXERB")
      (value "27k")
      (footprint "eagle-import:0204_7")
      (libsource (lib "eagle-import") (part "R-EU_0204/7"))
    )
    (comp (ref "RIN3_MIXERA")
      (value "27k")
      (footprint "eagle-import:0204_7")
      (libsource (lib "eagle-import") (part "R-EU_0204/7"))
    )
    (comp (ref "RIN3_MIXERB")
      (value "27k")
      (footprint "eagle-import:0204_7")
      (libsource (lib "eagle-import") (part "R-EU_0204/7"))
    )
    (comp (ref "RIN4_MIXERA")
      (value "27k")
      (footprint "eagle-import:0204_7")
      (libsource (lib "eagle-import") (part "R-EU_0204/7"))
    )
    (comp (ref "RIN4_MIXERB")
      (value "27k")
      (footprint "eagle-import:0204_7")
      (libsource (lib "eagle-import") (part "R-EU_0204/7"))
    )
    (comp (ref "RIN4_MIXERB1")
      (value "27k")
      (footprint "eagle-import:0204_7")
      (libsource (lib "eagle-import") (part "R-EU_0204/7"))
    )
    (comp (ref "RMODE_MIXERA")
      (value "8.2k")
      (footprint "eagle-import:0204_7")
      (libsource (lib "eagle-import") (part "R-EU_0204/7"))
    )
    (comp (ref "RMODE_MIXERB")
      (value "8.2k")
      (footprint "eagle-import:0204_7")
      (libsource (lib "eagle-import") (part "R-EU_0204/7"))
    )
    (comp (ref "ROUT_SUM_STG")
      (value "470")
      (footprint "eagle-import:0207_12")
      (libsource (lib "eagle-import") (part "R-EU_0207/12"))
    )
    (comp (ref "RRI_VCF")
      (value "51k")
      (footprint "eagle-import:0207_10")
      (libsource (lib "eagle-import") (part "R-EU_0207/10"))
    )
    (comp (ref "RSQU_2")
      (value "10k")
      (footprint "eagle-import:0204_7")
      (libsource (lib "eagle-import") (part "R-EU_0204/7"))
    )
    (comp (ref "RSTAB1_MIXERA")
      (value "470")
      (footprint "eagle-import:0204_7")
      (libsource (lib "eagle-import") (part "R-EU_0204/7"))
    )
    (comp (ref "RSTAB2_MIXERA")
      (value "470")
      (footprint "eagle-import:0207_10")
      (libsource (lib "eagle-import") (part "R-EU_0207/10"))
    )
    (comp (ref "RSTAB2_MIXERB")
      (value "470")
      (footprint "eagle-import:0207_10")
      (libsource (lib "eagle-import") (part "R-EU_0207/10"))
    )
    (comp (ref "RSTAB3_MIXERA")
      (value "470")
      (footprint "eagle-import:0204_7")
      (libsource (lib "eagle-import") (part "R-EU_0204/7"))
    )
    (comp (ref "RSTAB3_MIXERB")
      (value "470")
      (footprint "eagle-import:0204_7")
      (libsource (lib "eagle-import") (part "R-EU_0204/7"))
    )
    (comp (ref "RSTAB4_MIXERA")
      (value "470")
      (footprint "eagle-import:0204_7")
      (libsource (lib "eagle-import") (part "R-EU_0204/7"))
    )
    (comp (ref "RSTAB4_MIXERB")
      (value "470")
      (footprint "eagle-import:0204_7")
      (libsource (lib "eagle-import") (part "R-EU_0204/7"))
    )
    (comp (ref "RSTAB4_MIXERB1")
      (value "470")
      (footprint "eagle-import:0204_7")
      (libsource (lib "eagle-import") (part "R-EU_0204/7"))
    )
    (comp (ref "RSTAB4_MIXERB2")
      (value "470")
      (footprint "eagle-import:0204_7")
      (libsource (lib "eagle-import") (part "R-EU_0204/7"))
    )
    (comp (ref "RTEST_13700FREQ2")
      (value "27k")
      (footprint "eagle-import:0204_7")
      (libsource (lib "eagle-import") (part "R-EU_0204/7"))
    )
    (comp (ref "RTEST_LOG2")
      (value "1k")
      (footprint "eagle-import:0204_7")
      (libsource (lib "eagle-import") (part "R-EU_0204/7"))
    )
    (comp (ref "RTRI_2")
      (value "12k")
      (footprint "eagle-import:0204_7")
      (libsource (lib "eagle-import") (part "R-EU_0204/7"))
    )
    (comp (ref "R_CONV_ITOV_OUT")
      (value "33K")
      (footprint "eagle-import:0204_7")
      (libsource (lib "eagle-import") (part "R-EU_0204/7"))
    )
    (comp (ref "R_CV_FREQ1")
      (value "68k")
      (footprint "eagle-import:0204_7")
      (libsource (lib "eagle-import") (part "R-EU_0204/7"))
    )
    (comp (ref "R_CV_FREQ3")
      (value "68k")
      (footprint "eagle-import:0204_7")
      (libsource (lib "eagle-import") (part "R-EU_0204/7"))
    )
    (comp (ref "R_CV_FREQ_BIAS1")
      (value "270k")
      (footprint "eagle-import:0204_7")
      (libsource (lib "eagle-import") (part "R-EU_0204/7"))
    )
    (comp (ref "R_CV_FREQ_BIAS3")
      (value "270k")
      (footprint "eagle-import:0204_7")
      (libsource (lib "eagle-import") (part "R-EU_0204/7"))
    )
    (comp (ref "R_CV_FREQ_STAB1")
      (value "470")
      (footprint "eagle-import:0204_7")
      (libsource (lib "eagle-import") (part "R-EU_0204/7"))
    )
    (comp (ref "R_CV_FREQ_STAB3")
      (value "470")
      (footprint "eagle-import:0204_7")
      (libsource (lib "eagle-import") (part "R-EU_0204/7"))
    )
    (comp (ref "R_GAIN_VCA")
      (value "47k")
      (footprint "eagle-import:0204_7")
      (libsource (lib "eagle-import") (part "R-EU_0204/7"))
    )
    (comp (ref "R_LIM_2")
      (value "1k")
      (footprint "eagle-import:0204_7")
      (libsource (lib "eagle-import") (part "R-EU_0204/7"))
    )
    (comp (ref "R_PD_4TH_ORDER_VCF")
      (value "100k")
      (footprint "eagle-import:0204_7")
      (libsource (lib "eagle-import") (part "R-EU_0204/7"))
    )
    (comp (ref "R_PD_411_IN_PULSE1")
      (value "100k")
      (footprint "eagle-import:0207_10")
      (libsource (lib "eagle-import") (part "R-EU_0207/10"))
    )
    (comp (ref "R_PD_411_IN_SAW1")
      (value "100k")
      (footprint "eagle-import:0204_7")
      (libsource (lib "eagle-import") (part "R-EU_0204/7"))
    )
    (comp (ref "R_PD_411_IN_SYNC1")
      (value "100k")
      (footprint "eagle-import:0204_7")
      (libsource (lib "eagle-import") (part "R-EU_0204/7"))
    )
    (comp (ref "R_PD_411_IN_TRI1")
      (value "100k")
      (footprint "eagle-import:0204_7")
      (libsource (lib "eagle-import") (part "R-EU_0204/7"))
    )
    (comp (ref "R_RES_VCF")
      (value "100k")
      (footprint "eagle-import:0204_7")
      (libsource (lib "eagle-import") (part "R-EU_0204/7"))
    )
    (comp (ref "R_RST")
      (value "10k")
      (footprint "eagle-import:0207_10")
      (libsource (lib "eagle-import") (part "R-US_0207/10"))
    )
    (comp (ref "R_SW1A")
      (value "10k")
      (footprint "eagle-import:0207_10")
      (libsource (lib "eagle-import") (part "R-US_0207/10"))
    )
    (comp (ref "R_SW1B")
      (value "10k")
      (footprint "eagle-import:0207_10")
      (libsource (lib "eagle-import") (part "R-US_0207/10"))
    )
    (comp (ref "R_SW2A")
      (value "10k")
      (footprint "eagle-import:0207_10")
      (libsource (lib "eagle-import") (part "R-US_0207/10"))
    )
    (comp (ref "R_SW2B")
      (value "10k")
      (footprint "eagle-import:0207_10")
      (libsource (lib "eagle-import") (part "R-US_0207/10"))
    )
    (comp (ref "R_SYNC1")
      (value "470k")
      (footprint "eagle-import:0204_7")
      (libsource (lib "eagle-import") (part "R-EU_0204/7"))
    )
    (comp (ref "R_SYNC3")
      (value "470k")
      (footprint "eagle-import:0204_7")
      (libsource (lib "eagle-import") (part "R-EU_0204/7"))
    )
    (comp (ref "S1")
      (value "10-XX")
      (footprint "eagle-import:B3F-10XX")
      (fields (field (name "MPN") "B3F-1000"))
      (libsource (lib "eagle-import") (part "10-XX"))
    )
    (comp (ref "S2")
      (value "10-XX")
      (footprint "eagle-import:B3F-10XX")
      (fields (field (name "MPN") "B3F-1000"))
      (libsource (lib "eagle-import") (part "10-XX"))
    )
    (comp (ref "STM32L432KC_CONN_")
      (value "NUCLEO-F303K8")
      (footprint "eagle-import:MODULE_NUCLEO-F303K8")
      (fields (field (name "DIGI-KEY_PART_NUMBER") "497-15981-ND") (field (name "MF") "STMicroelectronics"))
      (libsource (lib "eagle-import") (part "NUCLEO-F303K8"))
    )
    (comp (ref "SUBBASS2")
      (value "HEF4027BP")
      (footprint "eagle-import:DIP254P762X420-16")
      (fields (field (name "MF") "NXP Semiconductors"))
      (libsource (lib "eagle-import") (part "HEF4027BP"))
    )
    (comp (ref "SUM_STG_C")
      (value "560p")
      (footprint "eagle-import:C075-032X103")
      (libsource (lib "eagle-import") (part "rcl_334_C-EU075-032X103"))
    )
    (comp (ref "SUM_STG_HEADER")
      (value "MA04-2")
      (footprint "eagle-import:MA04-2")
      (libsource (lib "eagle-import") (part "MA04-2"))
    )
    (comp (ref "SUM_STG_R")
      (value "27k")
      (footprint "eagle-import:0207_10")
      (libsource (lib "eagle-import") (part "R-EU_0207/10"))
    )
    (comp (ref "TP_13700_SQU2")
      (value "TESTPOINT")
      (footprint "eagle-import:TESTPOINT_63")
      (libsource (lib "eagle-import") (part "TESTPOINT"))
    )
    (comp (ref "TP_13700_TRI2")
      (value "TESTPOINT")
      (footprint "eagle-import:TESTPOINT_63")
      (libsource (lib "eagle-import") (part "TESTPOINT"))
    )
    (comp (ref "TP_CV_2")
      (value "TESTPOINT")
      (footprint "eagle-import:TESTPOINT_63")
      (libsource (lib "eagle-import") (part "TESTPOINT"))
    )
    (comp (ref "TP_PULSE1")
      (value "TESTPOINT")
      (footprint "eagle-import:TESTPOINT_63")
      (libsource (lib "eagle-import") (part "TESTPOINT"))
    )
    (comp (ref "TP_PULSE3")
      (value "TESTPOINT")
      (footprint "eagle-import:TESTPOINT_63")
      (libsource (lib "eagle-import") (part "TESTPOINT"))
    )
    (comp (ref "TP_SAW1")
      (value "TESTPOINT")
      (footprint "eagle-import:TESTPOINT_63")
      (libsource (lib "eagle-import") (part "TESTPOINT"))
    )
    (comp (ref "TP_SAW3")
      (value "TESTPOINT")
      (footprint "eagle-import:TESTPOINT_63")
      (libsource (lib "eagle-import") (part "TESTPOINT"))
    )
    (comp (ref "TP_TRI1")
      (value "TESTPOINT")
      (footprint "eagle-import:TESTPOINT_63")
      (libsource (lib "eagle-import") (part "TESTPOINT"))
    )
    (comp (ref "TP_TRI3")
      (value "TESTPOINT")
      (footprint "eagle-import:TESTPOINT_63")
      (libsource (lib "eagle-import") (part "TESTPOINT"))
    )
    (comp (ref "U1")
      (value "ANALOG_DEVICES_AD5391BSTZ-3ANALOG_DEVICES_AD5391BSTZ-3_0_0")
      (footprint "eagle-import:ANALOG_DEVICES_AD5391BSTZ-3_0")
      (fields (field (name "MF") "Analog Devices") (field (name "MPN") "AD5391BSTZ-3"))
      (libsource (lib "eagle-import") (part "ANALOG_DEVICES_AD5391BSTZ-3ANALOG_DEVICES_AD5391BSTZ-3_0_0"))
    )
    (comp (ref "VCA")
      (value "LM13700N")
      (footprint "eagle-import:DIL16")
      (libsource (lib "eagle-import") (part "LM13700N"))
    )
    (comp (ref "VCF")
      (value "AS3320")
      (footprint "eagle-import:DIL18")
      (libsource (lib "eagle-import") (part "AS3320"))
    )
    (comp (ref "VCF_ANALOG_SW")
      (value "DG413DJN")
      (footprint "eagle-import:DIL16")
      (libsource (lib "eagle-import") (part "DG413DJN"))
    )
    (comp (ref "VCF_JUMPER")
      (value "MA04-1")
      (footprint "eagle-import:MA04-1")
      (libsource (lib "eagle-import") (part "MA04-1"))
    )
    (comp (ref "VCO2")
      (value "LM13700N")
      (footprint "eagle-import:DIL16")
      (libsource (lib "eagle-import") (part "LM13700N"))
    )
  )
  (nets
    (net (code "1") (name "+15V") (class "Default")
      (node (ref "3") (pin "13") (pinfunction "VDD_13") (pintype "power_in"))
      (node (ref "3340A") (pin "16") (pinfunction "VCC_16") (pintype "bidirectional"))
      (node (ref "3340B") (pin "16") (pinfunction "VCC_16") (pintype "bidirectional"))
      (node (ref "C+15VPOL_VCF") (pin "2") (pinfunction "2_2") (pintype "passive"))
      (node (ref "C+15V_SUM_STG") (pin "2") (pinfunction "2_2") (pintype "passive"))
      (node (ref "C+15V_VCF") (pin "2") (pinfunction "2_2") (pintype "passive"))
      (node (ref "CDEC+15V6") (pin "1") (pinfunction "1_1") (pintype "passive"))
      (node (ref "CDEC+15V7") (pin "1") (pinfunction "1_1") (pintype "passive"))
      (node (ref "CDEC+15VPOL_MIXERB") (pin "2") (pinfunction "2_2") (pintype "passive"))
      (node (ref "CDEC+15V_MIXERB") (pin "2") (pinfunction "2_2") (pintype "passive"))
      (node (ref "CDEC_3340A2") (pin "2") (pinfunction "2_2") (pintype "passive"))
      (node (ref "CDEC_3340A3") (pin "2") (pinfunction "2_2") (pintype "passive"))
      (node (ref "CDEC_3340A6") (pin "2") (pinfunction "2_2") (pintype "passive"))
      (node (ref "CDEC_3340A7") (pin "2") (pinfunction "2_2") (pintype "passive"))
      (node (ref "CONV_ITOV_OUT") (pin "7") (pinfunction "V+_7") (pintype "power_in"))
      (node (ref "EXPCONV2") (pin "7") (pinfunction "V+_7") (pintype "power_in"))
      (node (ref "MIXER_A") (pin "16") (pinfunction "V+_16") (pintype "bidirectional"))
      (node (ref "MIXER_B") (pin "16") (pinfunction "V+_16") (pintype "bidirectional"))
      (node (ref "OPAMP_SUM_STG") (pin "7") (pinfunction "V+_7") (pintype "power_in"))
      (node (ref "R2_PWM1") (pin "2") (pinfunction "2_2") (pintype "passive"))
      (node (ref "R2_PWM3") (pin "2") (pinfunction "2_2") (pintype "passive"))
      (node (ref "R4_VCA") (pin "1") (pinfunction "1_1") (pintype "passive"))
      (node (ref "R8_1") (pin "2") (pinfunction "2_2") (pintype "passive"))
      (node (ref "R8_3") (pin "2") (pinfunction "2_2") (pintype "passive"))
      (node (ref "RMODE_MIXERA") (pin "1") (pinfunction "1_1") (pintype "passive"))
      (node (ref "RMODE_MIXERB") (pin "1") (pinfunction "1_1") (pintype "passive"))
      (node (ref "R_CV_FREQ_BIAS1") (pin "2") (pinfunction "2_2") (pintype "passive"))
      (node (ref "R_CV_FREQ_BIAS3") (pin "2") (pinfunction "2_2") (pintype "passive"))
      (node (ref "VCA") (pin "11") (pinfunction "V+_11") (pintype "power_in"))
      (node (ref "VCF") (pin "14") (pinfunction "V+_14") (pintype "bidirectional"))
      (node (ref "VCF_ANALOG_SW") (pin "13") (pinfunction "V+_13") (pintype "power_in"))
      (node (ref "VCO2") (pin "11") (pinfunction "V+_11") (pintype "power_in"))
    )
    (net (code "2") (name "-15V") (class "Default")
      (node (ref "3") (pin "4") (pinfunction "VSS_4") (pintype "power_in"))
      (node (ref "C-15V_SUM_STG") (pin "1") (pinfunction "1_1") (pintype "passive"))
      (node (ref "CDEC-15V6") (pin "2") (pinfunction "2_2") (pintype "passive"))
      (node (ref "CDEC-15V7") (pin "2") (pinfunction "2_2") (pintype "passive"))
      (node (ref "CDEC-15VPOL_MIXERB") (pin "1") (pinfunction "1_1") (pintype "passive"))
      (node (ref "CDEC-15V_MIXERB") (pin "1") (pinfunction "1_1") (pintype "passive"))
      (node (ref "CONV_ITOV_OUT") (pin "4") (pinfunction "V-_4") (pintype "power_in"))
      (node (ref "EXPCONV2") (pin "4") (pinfunction "V-_4") (pintype "power_in"))
      (node (ref "MIXER_A") (pin "9") (pinfunction "V-_9") (pintype "bidirectional"))
      (node (ref "MIXER_B") (pin "9") (pinfunction "V-_9") (pintype "bidirectional"))
      (node (ref "OPAMP_SUM_STG") (pin "4") (pinfunction "V-_4") (pintype "power_in"))
      (node (ref "R3_1") (pin "1") (pinfunction "1_1") (pintype "passive"))
      (node (ref "R3_3") (pin "1") (pinfunction "1_1") (pintype "passive"))
      (node (ref "RB1_VCF") (pin "1") (pinfunction "1_1") (pintype "passive"))
      (node (ref "RB2") (pin "1") (pinfunction "1_1") (pintype "passive"))
      (node (ref "RB3_VCF") (pin "1") (pinfunction "1_1") (pintype "passive"))
      (node (ref "RBIAS_EXPCONV2") (pin "1") (pinfunction "1_1") (pintype "passive"))
      (node (ref "REE_VCF") (pin "1") (pinfunction "1_1") (pintype "passive"))
      (node (ref "RSQU_2") (pin "1") (pinfunction "1_1") (pintype "passive"))
      (node (ref "RTRI_2") (pin "1") (pinfunction "1_1") (pintype "passive"))
      (node (ref "VCF_ANALOG_SW") (pin "4") (pinfunction "V-_4") (pintype "power_in"))
      (node (ref "VCO2") (pin "6") (pinfunction "V-_6") (pintype "power_in"))
    )
    (net (code "3") (name "5V") (class "Default")
      (node (ref "3") (pin "12") (pinfunction "VL_12") (pintype "power_in"))
      (node (ref "C5VPOL_VCF") (pin "1") (pinfunction "1_1") (pintype "passive"))
      (node (ref "C5V_VCF") (pin "1") (pinfunction "1_1") (pintype "passive"))
      (node (ref "CDEC_411B6") (pin "1") (pinfunction "1_1") (pintype "passive"))
      (node (ref "CDEC_411B7") (pin "1") (pinfunction "1_1") (pintype "passive"))
      (node (ref "CDEC_5V1") (pin "1") (pinfunction "1_1") (pintype "passive"))
      (node (ref "CDEC_5V4") (pin "1") (pinfunction "1_1") (pintype "passive"))
      (node (ref "CDEC_AVDD1") (pin "2") (pinfunction "2_2") (pintype "passive"))
      (node (ref "CDEC_AVDD1_100N") (pin "2") (pinfunction "2_2") (pintype "passive"))
      (node (ref "CDEC_AVDD2") (pin "2") (pinfunction "2_2") (pintype "passive"))
      (node (ref "CDEC_AVDD2_100N") (pin "2") (pinfunction "2_2") (pintype "passive"))
      (node (ref "CDEC_DVDD1") (pin "2") (pinfunction "2_2") (pintype "passive"))
      (node (ref "CDEC_DVDD2") (pin "2") (pinfunction "2_2") (pintype "passive"))
      (node (ref "CDEC_MCP") (pin "1") (pinfunction "1_1") (pintype "passive"))
      (node (ref "IC1") (pin "9") (pinfunction "VDD_9") (pintype "power_in"))
      (node (ref "IC_EEPROM") (pin "2") (pinfunction "A1_2") (pintype "input"))
      (node (ref "IC_EEPROM") (pin "3") (pinfunction "A2_3") (pintype "input"))
      (node (ref "IC_EEPROM") (pin "8") (pinfunction "VCC_8") (pintype "power_in"))
      (node (ref "R1_8") (pin "1") (pinfunction "1_1") (pintype "passive"))
      (node (ref "R3_EXPCONV2") (pin "2") (pinfunction "2_2") (pintype "passive"))
      (node (ref "R_PD_411_IN_SAW1") (pin "2") (pinfunction "2_2") (pintype "passive"))
      (node (ref "R_RST") (pin "1") (pinfunction "1_1") (pintype "passive"))
      (node (ref "R_SW1A") (pin "1") (pinfunction "1_1") (pintype "passive"))
      (node (ref "R_SW2A") (pin "1") (pinfunction "1_1") (pintype "passive"))
      (node (ref "STM32L432KC_CONN_") (pin "4.1") (pinfunction "VIN_4.1") (pintype "bidirectional"))
      (node (ref "SUBBASS2") (pin "11") (pinfunction "1K_11") (pintype "input"))
      (node (ref "SUBBASS2") (pin "16") (pinfunction "VDD_16") (pintype "power_in"))
      (node (ref "U1") (pin "1") (pinfunction "~{CLR}_1") (pintype "input"))
      (node (ref "U1") (pin "32") (pinfunction "AVDD_2_32") (pintype "power_in"))
      (node (ref "U1") (pin "42") (pinfunction "~{I2C}_42") (pintype "input"))
      (node (ref "U1") (pin "44") (pinfunction "1_DVDD_44") (pintype "power_in"))
      (node (ref "U1") (pin "45") (pinfunction "2_DVDD_45") (pintype "power_in"))
      (node (ref "U1") (pin "47") (pinfunction "3_DVDD_47") (pintype "power_in"))
      (node (ref "U1") (pin "8") (pinfunction "AVDD_1_8") (pintype "power_in"))
      (node (ref "VCF_ANALOG_SW") (pin "12") (pinfunction "VL_12") (pintype "input"))
    )
    (net (code "4") (name "411_IN_PULSE") (class "Default")
      (node (ref "3") (pin "8") (pinfunction "IN_8") (pintype "input"))
      (node (ref "IC1") (pin "22") (pinfunction "GPA1_22") (pintype "bidirectional"))
      (node (ref "R_PD_411_IN_PULSE1") (pin "2") (pinfunction "2_2") (pintype "passive"))
    )
    (net (code "5") (name "411_IN_SAW") (class "Default")
      (node (ref "3") (pin "9") (pinfunction "IN_9") (pintype "input"))
      (node (ref "IC1") (pin "23") (pinfunction "GPA2_23") (pintype "bidirectional"))
      (node (ref "R_PD_411_IN_SAW1") (pin "1") (pinfunction "1_1") (pintype "passive"))
    )
    (net (code "6") (name "411_IN_SYNC") (class "Default")
      (node (ref "3") (pin "16") (pinfunction "IN_16") (pintype "input"))
      (node (ref "IC1") (pin "24") (pinfunction "GPA3_24") (pintype "bidirectional"))
      (node (ref "R_PD_411_IN_SYNC1") (pin "1") (pinfunction "1_1") (pintype "passive"))
    )
    (net (code "7") (name "411_IN_TRI") (class "Default")
      (node (ref "3") (pin "1") (pinfunction "IN_1") (pintype "input"))
      (node (ref "IC1") (pin "21") (pinfunction "GPA0_21") (pintype "bidirectional"))
      (node (ref "R_PD_411_IN_TRI1") (pin "1") (pinfunction "1_1") (pintype "passive"))
    )
    (net (code "8") (name "2164_IN1_MIXA") (class "Default")
      (node (ref "MIXER_A") (pin "2") (pinfunction "I_IN_2") (pintype "bidirectional"))
      (node (ref "RIN1_MIXERA") (pin "1") (pinfunction "1_1") (pintype "passive"))
      (node (ref "RSTAB1_MIXERA") (pin "1") (pinfunction "1_1") (pintype "passive"))
    )
    (net (code "9") (name "2164_IN2_MIXA") (class "Default")
      (node (ref "MIXER_A") (pin "7") (pinfunction "I_IN_7") (pintype "bidirectional"))
      (node (ref "RIN2_MIXERA") (pin "1") (pinfunction "1_1") (pintype "passive"))
      (node (ref "RSTAB2_MIXERA") (pin "1") (pinfunction "1_1") (pintype "passive"))
    )
    (net (code "10") (name "2164_IN2_MIXB") (class "Default")
      (node (ref "MIXER_B") (pin "7") (pinfunction "I_IN_7") (pintype "bidirectional"))
      (node (ref "RIN2_MIXERB") (pin "1") (pinfunction "1_1") (pintype "passive"))
      (node (ref "RSTAB2_MIXERB") (pin "1") (pinfunction "1_1") (pintype "passive"))
    )
    (net (code "11") (name "2164_IN3_MIXA") (class "Default")
      (node (ref "MIXER_A") (pin "10") (pinfunction "I_IN_10") (pintype "bidirectional"))
      (node (ref "RIN3_MIXERA") (pin "1") (pinfunction "1_1") (pintype "passive"))
      (node (ref "RSTAB3_MIXERA") (pin "1") (pinfunction "1_1") (pintype "passive"))
    )
    (net (code "12") (name "2164_IN3_MIXB") (class "Default")
      (node (ref "MIXER_B") (pin "10") (pinfunction "I_IN_10") (pintype "bidirectional"))
      (node (ref "RIN3_MIXERB") (pin "1") (pinfunction "1_1") (pintype "passive"))
      (node (ref "RSTAB3_MIXERB") (pin "1") (pinfunction "1_1") (pintype "passive"))
    )
    (net (code "13") (name "2164_IN4_MIXA") (class "Default")
      (node (ref "MIXER_A") (pin "15") (pinfunction "I_IN_15") (pintype "bidirectional"))
      (node (ref "RIN4_MIXERA") (pin "1") (pinfunction "1_1") (pintype "passive"))
      (node (ref "RSTAB4_MIXERA") (pin "1") (pinfunction "1_1") (pintype "passive"))
    )
    (net (code "14") (name "2164_IN4_MIXB") (class "Default")
      (node (ref "MIXER_B") (pin "15") (pinfunction "I_IN_15") (pintype "bidirectional"))
      (node (ref "RIN4_MIXERB") (pin "1") (pinfunction "1_1") (pintype "passive"))
      (node (ref "RSTAB4_MIXERB") (pin "1") (pinfunction "1_1") (pintype "passive"))
    )
    (net (code "15") (name "2164_MODE_MIXA") (class "Default")
      (node (ref "MIXER_A") (pin "1") (pinfunction "MODE_1") (pintype "bidirectional"))
      (node (ref "RMODE_MIXERA") (pin "2") (pinfunction "2_2") (pintype "passive"))
    )
    (net (code "16") (name "2164_MODE_MIXB") (class "Default")
      (node (ref "MIXER_B") (pin "1") (pinfunction "MODE_1") (pintype "bidirectional"))
      (node (ref "RMODE_MIXERB") (pin "2") (pinfunction "2_2") (pintype "passive"))
    )
    (net (code "17") (name "2164_OUT2_MIXA") (class "Default")
      (node (ref "JP_MIXER_A") (pin "2") (pinfunction "2_2") (pintype "passive"))
      (node (ref "MIXER_A") (pin "5") (pinfunction "I_OUT_5") (pintype "bidirectional"))
    )
    (net (code "18") (name "2164_OUT2_MIXB") (class "Default")
      (node (ref "JP_MIXER_B") (pin "4") (pinfunction "4_4") (pintype "passive"))
      (node (ref "MIXER_B") (pin "5") (pinfunction "I_OUT_5") (pintype "bidirectional"))
    )
    (net (code "19") (name "2164_OUT3_MIXA") (class "Default")
      (node (ref "JP_MIXER_A") (pin "6") (pinfunction "6_6") (pintype "passive"))
      (node (ref "MIXER_A") (pin "12") (pinfunction "I_OUT_12") (pintype "bidirectional"))
    )
    (net (code "20") (name "2164_OUT4_MIXA") (class "Default")
      (node (ref "JP_MIXER_A") (pin "8") (pinfunction "8_8") (pintype "passive"))
      (node (ref "MIXER_A") (pin "13") (pinfunction "I_OUT_13") (pintype "bidirectional"))
    )
    (net (code "21") (name "2164_OUT4_MIXB") (class "Default")
      (node (ref "JP_MIXER_B") (pin "6") (pinfunction "6_6") (pintype "passive"))
      (node (ref "MIXER_B") (pin "13") (pinfunction "I_OUT_13") (pintype "bidirectional"))
    )
    (net (code "22") (name "AGND") (class "Default")
      (node (ref "3") (pin "5") (pinfunction "GND_5") (pintype "power_in"))
      (node (ref "3340A") (pin "12") (pinfunction "GND_12") (pintype "bidirectional"))
      (node (ref "3340B") (pin "12") (pinfunction "GND_12") (pintype "bidirectional"))
      (node (ref "C+15VPOL_VCF") (pin "1") (pinfunction "1_1") (pintype "passive"))
      (node (ref "C+15V_SUM_STG") (pin "1") (pinfunction "1_1") (pintype "passive"))
      (node (ref "C+15V_VCF") (pin "1") (pinfunction "1_1") (pintype "passive"))
      (node (ref "C-15VPOL_VCF") (pin "2") (pinfunction "2_2") (pintype "passive"))
      (node (ref "C-15V_SUM_STG") (pin "2") (pinfunction "2_2") (pintype "passive"))
      (node (ref "C-15V_VCF") (pin "2") (pinfunction "2_2") (pintype "passive"))
      (node (ref "C10") (pin "1") (pinfunction "1_1") (pintype "passive"))
      (node (ref "C1_VCA") (pin "2") (pinfunction "2_2") (pintype "passive"))
      (node (ref "C2_SYNC1") (pin "1") (pinfunction "1_1") (pintype "passive"))
      (node (ref "C2_SYNC3") (pin "1") (pinfunction "1_1") (pintype "passive"))
      (node (ref "C3") (pin "1") (pinfunction "1_1") (pintype "passive"))
      (node (ref "C4") (pin "1") (pinfunction "1_1") (pintype "passive"))
      (node (ref "C4_1") (pin "2") (pinfunction "2_2") (pintype "passive"))
      (node (ref "C4_3") (pin "2") (pinfunction "2_2") (pintype "passive"))
      (node (ref "C5") (pin "1") (pinfunction "1_1") (pintype "passive"))
      (node (ref "C5VPOL_VCF") (pin "2") (pinfunction "2_2") (pintype "passive"))
      (node (ref "C5V_VCF") (pin "2") (pinfunction "2_2") (pintype "passive"))
      (node (ref "CDEC+15V6") (pin "2") (pinfunction "2_2") (pintype "passive"))
      (node (ref "CDEC+15V7") (pin "2") (pinfunction "2_2") (pintype "passive"))
      (node (ref "CDEC+15VPOL_MIXERB") (pin "1") (pinfunction "1_1") (pintype "passive"))
      (node (ref "CDEC+15V_MIXERB") (pin "1") (pinfunction "1_1") (pintype "passive"))
      (node (ref "CDEC-15V6") (pin "1") (pinfunction "1_1") (pintype "passive"))
      (node (ref "CDEC-15V7") (pin "1") (pinfunction "1_1") (pintype "passive"))
      (node (ref "CDEC-15VPOL_MIXERB") (pin "2") (pinfunction "2_2") (pintype "passive"))
      (node (ref "CDEC-15V_MIXERB") (pin "2") (pinfunction "2_2") (pintype "passive"))
      (node (ref "CDEC_3340A2") (pin "1") (pinfunction "1_1") (pintype "passive"))
      (node (ref "CDEC_3340A3") (pin "1") (pinfunction "1_1") (pintype "passive"))
      (node (ref "CDEC_3340A6") (pin "1") (pinfunction "1_1") (pintype "passive"))
      (node (ref "CDEC_3340A7") (pin "1") (pinfunction "1_1") (pintype "passive"))
      (node (ref "CDEC_3340B2") (pin "1") (pinfunction "1_1") (pintype "passive"))
      (node (ref "CDEC_3340B3") (pin "1") (pinfunction "1_1") (pintype "passive"))
      (node (ref "CDEC_3340B6") (pin "1") (pinfunction "1_1") (pintype "passive"))
      (node (ref "CDEC_3340B7") (pin "1") (pinfunction "1_1") (pintype "passive"))
      (node (ref "CDEC_411B6") (pin "2") (pinfunction "2_2") (pintype "passive"))
      (node (ref "CDEC_411B7") (pin "2") (pinfunction "2_2") (pintype "passive"))
      (node (ref "CDEC_5V1") (pin "2") (pinfunction "2_2") (pintype "passive"))
      (node (ref "CDEC_5V4") (pin "2") (pinfunction "2_2") (pintype "passive"))
      (node (ref "CDEC_AVDD1") (pin "1") (pinfunction "1_1") (pintype "passive"))
      (node (ref "CDEC_AVDD1_100N") (pin "1") (pinfunction "1_1") (pintype "passive"))
      (node (ref "CDEC_AVDD2") (pin "1") (pinfunction "1_1") (pintype "passive"))
      (node (ref "CDEC_AVDD2_100N") (pin "1") (pinfunction "1_1") (pintype "passive"))
      (node (ref "CDEC_DVDD1") (pin "1") (pinfunction "1_1") (pintype "passive"))
      (node (ref "CDEC_DVDD2") (pin "1") (pinfunction "1_1") (pintype "passive"))
      (node (ref "CDEC_MCP") (pin "2") (pinfunction "2_2") (pintype "passive"))
      (node (ref "CDEC_VREF") (pin "2") (pinfunction "2_2") (pintype "passive"))
      (node (ref "CF_2") (pin "1") (pinfunction "1_1") (pintype "passive"))
      (node (ref "CONN_UART_RPI") (pin "1") (pinfunction "1_1") (pintype "passive"))
      (node (ref "CONV_ITOV_OUT") (pin "3") (pinfunction "+IN_3") (pintype "input"))
      (node (ref "CSTAB1_MIXERA") (pin "1") (pinfunction "1_1") (pintype "passive"))
      (node (ref "CSTAB2_MIXERA") (pin "1") (pinfunction "1_1") (pintype "passive"))
      (node (ref "CSTAB2_MIXERB") (pin "1") (pinfunction "1_1") (pintype "passive"))
      (node (ref "CSTAB3") (pin "1") (pinfunction "1_1") (pintype "passive"))
      (node (ref "CSTAB3_MIXERA") (pin "1") (pinfunction "1_1") (pintype "passive"))
      (node (ref "CSTAB3_MIXERB") (pin "1") (pinfunction "1_1") (pintype "passive"))
      (node (ref "CSTAB4_MIXERA") (pin "1") (pinfunction "1_1") (pintype "passive"))
      (node (ref "CSTAB8") (pin "1") (pinfunction "1_1") (pintype "passive"))
      (node (ref "C_1") (pin "1") (pinfunction "1_1") (pintype "passive"))
      (node (ref "C_3") (pin "1") (pinfunction "1_1") (pintype "passive"))
      (node (ref "C_CV_FREQ_STAB1") (pin "1") (pinfunction "1_1") (pintype "passive"))
      (node (ref "C_CV_FREQ_STAB3") (pin "1") (pinfunction "1_1") (pintype "passive"))
      (node (ref "C_SW1") (pin "2") (pinfunction "2_2") (pintype "passive"))
      (node (ref "C_SW2") (pin "2") (pinfunction "2_2") (pintype "passive"))
      (node (ref "EXPCONV2") (pin "3") (pinfunction "+IN_3") (pintype "input"))
      (node (ref "IC1") (pin "10") (pinfunction "VSS_10") (pintype "power_in"))
      (node (ref "IC1") (pin "15") (pinfunction "A0_15") (pintype "input"))
      (node (ref "IC1") (pin "16") (pinfunction "A1_16") (pintype "input"))
      (node (ref "IC1") (pin "17") (pinfunction "A2_17") (pintype "input"))
      (node (ref "IC_EEPROM") (pin "1") (pinfunction "A0_1") (pintype "input"))
      (node (ref "IC_EEPROM") (pin "4") (pinfunction "GND_4") (pintype "power_in"))
      (node (ref "IC_EEPROM") (pin "7") (pinfunction "WP_7") (pintype "input"))
      (node (ref "MIXER_A") (pin "8") (pinfunction "GND_8") (pintype "bidirectional"))
      (node (ref "MIXER_B") (pin "8") (pinfunction "GND_8") (pintype "bidirectional"))
      (node (ref "OUT") (pin "2") (pinfunction "2_2") (pintype "passive"))
      (node (ref "POT_SUM_STG") (pin "1") (pinfunction "A_1") (pintype "passive"))
      (node (ref "R11_1") (pin "2") (pinfunction "2_2") (pintype "passive"))
      (node (ref "R11_3") (pin "2") (pinfunction "2_2") (pintype "passive"))
      (node (ref "R1_7") (pin "1") (pinfunction "1_1") (pintype "passive"))
      (node (ref "R1_PWM1") (pin "2") (pinfunction "2_2") (pintype "passive"))
      (node (ref "R1_PWM3") (pin "2") (pinfunction "2_2") (pintype "passive"))
      (node (ref "R1_VCF") (pin "2") (pinfunction "2_2") (pintype "passive"))
      (node (ref "R2_7") (pin "1") (pinfunction "1_1") (pintype "passive"))
      (node (ref "R2_8") (pin "2") (pinfunction "2_2") (pintype "passive"))
      (node (ref "R2_EXPCONV2") (pin "2") (pinfunction "2_2") (pintype "passive"))
      (node (ref "R2_VCA") (pin "1") (pinfunction "1_1") (pintype "passive"))
      (node (ref "R3_4") (pin "1") (pinfunction "1_1") (pintype "passive"))
      (node (ref "R3_VCA") (pin "2") (pinfunction "2_2") (pintype "passive"))
      (node (ref "R4_EXPCONV2") (pin "2") (pinfunction "2_2") (pintype "passive"))
      (node (ref "R5_1") (pin "2") (pinfunction "2_2") (pintype "passive"))
      (node (ref "R5_3") (pin "2") (pinfunction "2_2") (pintype "passive"))
      (node (ref "RA_2") (pin "1") (pinfunction "1_1") (pintype "passive"))
      (node (ref "RCAL_2") (pin "2") (pinfunction "2_2") (pintype "passive"))
      (node (ref "REE_2") (pin "2") (pinfunction "2_2") (pintype "passive"))
      (node (ref "RSTAB4_MIXERB1") (pin "1") (pinfunction "1_1") (pintype "passive"))
      (node (ref "RTEST_LOG2") (pin "2") (pinfunction "2_2") (pintype "passive"))
      (node (ref "R_PD_411_IN_PULSE1") (pin "1") (pinfunction "1_1") (pintype "passive"))
      (node (ref "R_PD_411_IN_SYNC1") (pin "2") (pinfunction "2_2") (pintype "passive"))
      (node (ref "R_PD_411_IN_TRI1") (pin "2") (pinfunction "2_2") (pintype "passive"))
      (node (ref "R_PD_4TH_ORDER_VCF") (pin "1") (pinfunction "1_1") (pintype "passive"))
      (node (ref "R_SYNC1") (pin "1") (pinfunction "1_1") (pintype "passive"))
      (node (ref "R_SYNC3") (pin "1") (pinfunction "1_1") (pintype "passive"))
      (node (ref "S1") (pin "1") (pinfunction "S_1") (pintype "passive"))
      (node (ref "S1") (pin "2") (pinfunction "S1_2") (pintype "passive"))
      (node (ref "S2") (pin "1") (pinfunction "S_1") (pintype "passive"))
      (node (ref "S2") (pin "2") (pinfunction "S1_2") (pintype "passive"))
      (node (ref "STM32L432KC_CONN_") (pin "3.4") (pinfunction "GND_3.4") (pintype "bidirectional"))
      (node (ref "STM32L432KC_CONN_") (pin "4.2") (pinfunction "GND_4.2") (pintype "bidirectional"))
      (node (ref "SUBBASS2") (pin "12") (pinfunction "1CD_12") (pintype "input"))
      (node (ref "SUBBASS2") (pin "8") (pinfunction "VSS_8") (pintype "passive"))
      (node (ref "SUBBASS2") (pin "9") (pinfunction "1SD_9") (pintype "input"))
      (node (ref "U1") (pin "14") (pinfunction "AGND_1_14") (pintype "power_in"))
      (node (ref "U1") (pin "26") (pinfunction "DAC_GND_2_26") (pintype "power_in"))
      (node (ref "U1") (pin "27") (pinfunction "SIGNAL_GND_2_27") (pintype "power_in"))
      (node (ref "U1") (pin "31") (pinfunction "AGND_2_31") (pintype "power_in"))
      (node (ref "U1") (pin "4") (pinfunction "REF_GND_4") (pintype "power_in"))
      (node (ref "U1") (pin "40") (pinfunction "DCEN/AD1_40") (pintype "input"))
      (node (ref "U1") (pin "41") (pinfunction "PD_41") (pintype "input"))
      (node (ref "U1") (pin "43") (pinfunction "1_DGND_43") (pintype "power_in"))
      (node (ref "U1") (pin "46") (pinfunction "2_DGND_46") (pintype "power_in"))
      (node (ref "U1") (pin "52") (pinfunction "3_DGND_52") (pintype "power_in"))
      (node (ref "U1") (pin "6") (pinfunction "SIGNAL_GND_1_6") (pintype "power_in"))
      (node (ref "U1") (pin "7") (pinfunction "DAC_GND_1_7") (pintype "power_in"))
      (node (ref "VCA") (pin "6") (pinfunction "V-_6") (pintype "power_in"))
      (node (ref "VCF") (pin "3") (pinfunction "GND_3") (pintype "bidirectional"))
      (node (ref "VCF_ANALOG_SW") (pin "5") (pinfunction "GND_5") (pintype "power_in"))
      (node (ref "VCO2") (pin "4") (pinfunction "IN_N_4") (pintype "input"))
    )
    (net (code "23") (name "BIAS_4027_VCO13700") (class "Default")
      (node (ref "CIN_2") (pin "1") (pinfunction "1_1") (pintype "passive"))
      (node (ref "D_2") (pin "A") (pinfunction "A_A") (pintype "passive"))
      (node (ref "R1_8") (pin "2") (pinfunction "2_2") (pintype "passive"))
      (node (ref "R2_8") (pin "1") (pinfunction "1_1") (pintype "passive"))
    )
    (net (code "24") (name "BIAS_VCA") (class "Default")
      (node (ref "C1_VCA") (pin "1") (pinfunction "1_1") (pintype "passive"))
      (node (ref "C2_VCA") (pin "1") (pinfunction "1_1") (pintype "passive"))
      (node (ref "OPAMP_SUM_STG") (pin "3") (pinfunction "+IN_3") (pintype "input"))
      (node (ref "R3_VCA") (pin "1") (pinfunction "1_1") (pintype "passive"))
      (node (ref "R4_VCA") (pin "2") (pinfunction "2_2") (pintype "passive"))
      (node (ref "R5_VCA") (pin "1") (pinfunction "1_1") (pintype "passive"))
      (node (ref "VCA") (pin "3") (pinfunction "IN_P_3") (pintype "input"))
    )
    (net (code "25") (name "CALIB_3340A") (class "Default")
      (node (ref "R5_3") (pin "1") (pinfunction "1_1") (pintype "passive"))
      (node (ref "R6_3") (pin "1") (pinfunction "1_1") (pintype "passive"))
      (node (ref "STM32L432KC_CONN_") (pin "3.12") (pinfunction "PA8_3.12") (pintype "bidirectional"))
    )
    (net (code "26") (name "CALIB_3340B") (class "Default")
      (node (ref "R5_1") (pin "1") (pinfunction "1_1") (pintype "passive"))
      (node (ref "R6_1") (pin "1") (pinfunction "1_1") (pintype "passive"))
      (node (ref "STM32L432KC_CONN_") (pin "3.1") (pinfunction "PA9_3.1") (pintype "bidirectional"))
    )
    (net (code "27") (name "CALIB_13700") (class "Default")
      (node (ref "RCAL_1") (pin "2") (pinfunction "2_2") (pintype "passive"))
      (node (ref "RCAL_2") (pin "1") (pinfunction "1_1") (pintype "passive"))
      (node (ref "STM32L432KC_CONN_") (pin "3.2") (pinfunction "PA10_3.2") (pintype "bidirectional"))
    )
    (net (code "28") (name "CAP1_VCF") (class "Default")
      (node (ref "C3") (pin "2") (pinfunction "2_2") (pintype "passive"))
      (node (ref "VCF") (pin "5") (pinfunction "CAP_5") (pintype "bidirectional"))
    )
    (net (code "29") (name "CAP2_VCF") (class "Default")
      (node (ref "C5") (pin "2") (pinfunction "2_2") (pintype "passive"))
      (node (ref "VCF") (pin "4") (pinfunction "CAP_4") (pintype "bidirectional"))
    )
    (net (code "30") (name "CAP3_VCF") (class "Default")
      (node (ref "C4") (pin "2") (pinfunction "2_2") (pintype "passive"))
      (node (ref "VCF") (pin "16") (pinfunction "CAP_16") (pintype "bidirectional"))
    )
    (net (code "31") (name "CAP4_VCF") (class "Default")
      (node (ref "C10") (pin "2") (pinfunction "2_2") (pintype "passive"))
      (node (ref "VCF") (pin "11") (pinfunction "CAP_11") (pintype "bidirectional"))
    )
    (net (code "32") (name "CV_CUTOFF") (class "Default")
      (node (ref "R2_VCF") (pin "2") (pinfunction "2_2") (pintype "passive"))
      (node (ref "U1") (pin "28") (pinfunction "VOUT_13_28") (pintype "tri_state"))
    )
    (net (code "33") (name "CV_FREQ_3340A") (class "Default")
      (node (ref "JP_FMLIN_VCO3340B1") (pin "1") (pinfunction "1_1") (pintype "passive"))
      (node (ref "R_CV_FREQ3") (pin "2") (pinfunction "2_2") (pintype "passive"))
      (node (ref "U1") (pin "12") (pinfunction "VOUT_3_12") (pintype "tri_state"))
    )
    (net (code "34") (name "CV_FREQ_3340B") (class "Default")
      (node (ref "R_CV_FREQ1") (pin "2") (pinfunction "2_2") (pintype "passive"))
      (node (ref "U1") (pin "9") (pinfunction "VOUT_0_9") (pintype "tri_state"))
    )
    (net (code "35") (name "CV_FREQ_13700") (class "Default")
      (node (ref "R1_EXPCONV2") (pin "2") (pinfunction "2_2") (pintype "passive"))
      (node (ref "TP_CV_2") (pin "P$1") (pinfunction "P$1_P$1") (pintype "passive"))
      (node (ref "U1") (pin "11") (pinfunction "VOUT_2_11") (pintype "tri_state"))
    )
    (net (code "36") (name "CV_PWM_3340A") (class "Default")
      (node (ref "3340A") (pin "5") (pinfunction "PWM_CTRL_5") (pintype "bidirectional"))
      (node (ref "R1_PWM3") (pin "1") (pinfunction "1_1") (pintype "passive"))
      (node (ref "R2_PWM3") (pin "1") (pinfunction "1_1") (pintype "passive"))
      (node (ref "U1") (pin "13") (pinfunction "VOUT_4_13") (pintype "tri_state"))
    )
    (net (code "37") (name "CV_PWM_3340B") (class "Default")
      (node (ref "3340B") (pin "5") (pinfunction "PWM_CTRL_5") (pintype "bidirectional"))
      (node (ref "R1_PWM1") (pin "1") (pinfunction "1_1") (pintype "passive"))
      (node (ref "R2_PWM1") (pin "1") (pinfunction "1_1") (pintype "passive"))
      (node (ref "U1") (pin "10") (pinfunction "VOUT_1_10") (pintype "tri_state"))
    )
    (net (code "38") (name "CV_RES") (class "Default")
      (node (ref "R_RES_VCF") (pin "2") (pinfunction "2_2") (pintype "passive"))
      (node (ref "U1") (pin "29") (pinfunction "VOUT_14_29") (pintype "tri_state"))
    )
    (net (code "39") (name "CV_VCA") (class "Default")
      (node (ref "R_GAIN_VCA") (pin "1") (pinfunction "1_1") (pintype "passive"))
      (node (ref "U1") (pin "30") (pinfunction "VOUT_15_30") (pintype "tri_state"))
    )
    (net (code "40") (name "DAC_BUSY") (class "Default")
      (node (ref "STM32L432KC_CONN_") (pin "4.9") (pinfunction "PA4_4.9") (pintype "bidirectional"))
      (node (ref "U1") (pin "38") (pinfunction "~{BUSY}_38") (pintype "output"))
    )
    (net (code "41") (name "DAC_LDAC") (class "Default")
      (node (ref "STM32L432KC_CONN_") (pin "4.8") (pinfunction "PA5_4.8") (pintype "bidirectional"))
      (node (ref "U1") (pin "39") (pinfunction "~{LDAC}_39") (pintype "input"))
    )
    (net (code "42") (name "DAC_SYNC") (class "Default")
      (node (ref "STM32L432KC_CONN_") (pin "4.10") (pinfunction "PA3_4.10") (pintype "bidirectional"))
      (node (ref "U1") (pin "51") (pinfunction "~{SYNC}/AD0_51") (pintype "input"))
    )
    (net (code "43") (name "FM_ENTREE_13700_VCO13700") (class "Default")
      (node (ref "HEADER_EXPCONV2") (pin "3") (pinfunction "3_3") (pintype "passive"))
      (node (ref "RTEST_13700FREQ2") (pin "2") (pinfunction "2_2") (pintype "passive"))
      (node (ref "VCO2") (pin "1") (pinfunction "I_BIAS_1") (pintype "input"))
    )
    (net (code "44") (name "FREQ_CTRL_VCOA") (class "Default")
      (node (ref "3340A") (pin "15") (pinfunction "FREQ_CTRL_15") (pintype "bidirectional"))
      (node (ref "R_CV_FREQ3") (pin "1") (pinfunction "1_1") (pintype "passive"))
      (node (ref "R_CV_FREQ_BIAS3") (pin "1") (pinfunction "1_1") (pintype "passive"))
      (node (ref "R_CV_FREQ_STAB3") (pin "1") (pinfunction "1_1") (pintype "passive"))
    )
    (net (code "45") (name "FREQ_CTRL_VCOB") (class "Default")
      (node (ref "3340B") (pin "15") (pinfunction "FREQ_CTRL_15") (pintype "bidirectional"))
      (node (ref "R_CV_FREQ1") (pin "1") (pinfunction "1_1") (pintype "passive"))
      (node (ref "R_CV_FREQ_BIAS1") (pin "1") (pinfunction "1_1") (pintype "passive"))
      (node (ref "R_CV_FREQ_STAB1") (pin "1") (pinfunction "1_1") (pintype "passive"))
    )
    (net (code "46") (name "FREQ_CV_VCF") (class "Default")
      (node (ref "R1_VCF") (pin "1") (pinfunction "1_1") (pintype "passive"))
      (node (ref "R2_VCF") (pin "1") (pinfunction "1_1") (pintype "passive"))
      (node (ref "VCF") (pin "12") (pinfunction "FREQ_CV_12") (pintype "bidirectional"))
    )
    (net (code "47") (name "GAIN1_A") (class "Default")
      (node (ref "MIXER_A") (pin "3") (pinfunction "GAIN_VCA_3") (pintype "bidirectional"))
      (node (ref "U1") (pin "17") (pinfunction "VOUT_7_17") (pintype "tri_state"))
    )
    (net (code "48") (name "GAIN1_B") (class "Default")
      (node (ref "MIXER_B") (pin "3") (pinfunction "GAIN_VCA_3") (pintype "bidirectional"))
      (node (ref "U1") (pin "24") (pinfunction "VOUT_11_24") (pintype "tri_state"))
    )
    (net (code "49") (name "GAIN2_A") (class "Default")
      (node (ref "MIXER_A") (pin "6") (pinfunction "GAIN_VCA_6") (pintype "bidirectional"))
      (node (ref "U1") (pin "21") (pinfunction "VOUT_8_21") (pintype "tri_state"))
    )
    (net (code "50") (name "GAIN2_B") (class "Default")
      (node (ref "MIXER_B") (pin "6") (pinfunction "GAIN_VCA_6") (pintype "bidirectional"))
      (node (ref "U1") (pin "25") (pinfunction "VOUT_12_25") (pintype "tri_state"))
    )
    (net (code "51") (name "GAIN3_A") (class "Default")
      (node (ref "MIXER_A") (pin "11") (pinfunction "GAIN_VCA_11") (pintype "bidirectional"))
      (node (ref "U1") (pin "16") (pinfunction "VOUT_6_16") (pintype "tri_state"))
    )
    (net (code "52") (name "GAIN3_B") (class "Default")
      (node (ref "MIXER_B") (pin "11") (pinfunction "GAIN_VCA_11") (pintype "bidirectional"))
      (node (ref "U1") (pin "22") (pinfunction "VOUT_9_22") (pintype "tri_state"))
    )
    (net (code "53") (name "GAIN4_A") (class "Default")
      (node (ref "MIXER_A") (pin "14") (pinfunction "GAIN_VCA_14") (pintype "bidirectional"))
      (node (ref "U1") (pin "15") (pinfunction "VOUT_5_15") (pintype "tri_state"))
    )
    (net (code "54") (name "GAIN4_B") (class "Default")
      (node (ref "MIXER_B") (pin "14") (pinfunction "GAIN_VCA_14") (pintype "bidirectional"))
      (node (ref "U1") (pin "23") (pinfunction "VOUT_10_23") (pintype "tri_state"))
    )
    (net (code "55") (name "GPB_5") (class "Default")
      (node (ref "IC1") (pin "6") (pinfunction "GPB5_6") (pintype "bidirectional"))
    )
    (net (code "56") (name "GPB_6") (class "Default")
      (node (ref "IC1") (pin "7") (pinfunction "GPB6_7") (pintype "bidirectional"))
    )
    (net (code "57") (name "GPB_7") (class "Default")
      (node (ref "IC1") (pin "8") (pinfunction "GPB7_8") (pintype "bidirectional"))
    )
    (net (code "58") (name "HARD_SYNC_VCOA") (class "Default")
      (node (ref "3340A") (pin "6") (pinfunction "HARD_SYNC_6") (pintype "bidirectional"))
      (node (ref "C1_SYNC3") (pin "2") (pinfunction "2_2") (pintype "passive"))
    )
    (net (code "59") (name "HARD_SYNC_VCOB") (class "Default")
      (node (ref "3340B") (pin "6") (pinfunction "HARD_SYNC_6") (pintype "bidirectional"))
      (node (ref "C1_SYNC1") (pin "2") (pinfunction "2_2") (pintype "passive"))
    )
    (net (code "60") (name "IA_VCO13700") (class "Default")
      (node (ref "REE_2") (pin "1") (pinfunction "1_1") (pintype "passive"))
      (node (ref "VCO2") (pin "16") (pinfunction "I_BIAS_16") (pintype "input"))
    )
    (net (code "61") (name "IN1_MIXERA") (class "Default")
      (node (ref "CIN1_MIXERA") (pin "1") (pinfunction "1_1") (pintype "passive"))
      (node (ref "JP_TRIOUT_VCO3340B") (pin "2") (pinfunction "2_2") (pintype "passive"))
    )
    (net (code "62") (name "IN1_VCF") (class "Default")
      (node (ref "RC1_VCF") (pin "2") (pinfunction "2_2") (pintype "passive"))
      (node (ref "RF1_VCF") (pin "2") (pinfunction "2_2") (pintype "passive"))
      (node (ref "VCF") (pin "1") (pinfunction "IN_1") (pintype "bidirectional"))
    )
    (net (code "63") (name "IN2_MIXERA") (class "Default")
      (node (ref "CIN2_MIXERA") (pin "1") (pinfunction "1_1") (pintype "passive"))
      (node (ref "JP_OUT_VCO3340A") (pin "2") (pinfunction "2_2") (pintype "passive"))
      (node (ref "JP_OUT_VCO3340A2") (pin "1") (pinfunction "1_1") (pintype "passive"))
    )
    (net (code "64") (name "IN2_MIXERB") (class "Default")
      (node (ref "CIN2_MIXERB") (pin "1") (pinfunction "1_1") (pintype "passive"))
      (node (ref "JP8") (pin "2") (pinfunction "2_2") (pintype "passive"))
    )
    (net (code "65") (name "IN2_VCF") (class "Default")
      (node (ref "RB1_VCF") (pin "2") (pinfunction "2_2") (pintype "passive"))
      (node (ref "RC2_VCF") (pin "1") (pinfunction "1_1") (pintype "passive"))
      (node (ref "RF2_VCF") (pin "1") (pinfunction "1_1") (pintype "passive"))
      (node (ref "VCF") (pin "2") (pinfunction "IN_2") (pintype "bidirectional"))
    )
    (net (code "66") (name "IN3_MIXERA") (class "Default")
      (node (ref "CIN3_MIXERA") (pin "1") (pinfunction "1_1") (pintype "passive"))
      (node (ref "JP_SAWOUT_VCO3340B") (pin "2") (pinfunction "2_2") (pintype "passive"))
    )
    (net (code "67") (name "IN3_MIXERB") (class "Default")
      (node (ref "CIN3_MIXERB") (pin "1") (pinfunction "1_1") (pintype "passive"))
      (node (ref "JP9") (pin "2") (pinfunction "2_2") (pintype "passive"))
    )
    (net (code "68") (name "IN3_VCF") (class "Default")
      (node (ref "RB3_VCF") (pin "2") (pinfunction "2_2") (pintype "passive"))
      (node (ref "RC3") (pin "1") (pinfunction "1_1") (pintype "passive"))
      (node (ref "RF3") (pin "1") (pinfunction "1_1") (pintype "passive"))
      (node (ref "VCF") (pin "17") (pinfunction "IN_17") (pintype "bidirectional"))
    )
    (net (code "69") (name "IN4_MIXERA") (class "Default")
      (node (ref "CIN4_MIXERA") (pin "1") (pinfunction "1_1") (pintype "passive"))
      (node (ref "JP_PULSEOUT_VCO3340B") (pin "2") (pinfunction "2_2") (pintype "passive"))
    )
    (net (code "70") (name "IN4_MIXERB") (class "Default")
      (node (ref "CIN4_MIXERB") (pin "1") (pinfunction "1_1") (pintype "passive"))
      (node (ref "JP7") (pin "2") (pinfunction "2_2") (pintype "passive"))
    )
    (net (code "71") (name "IN4_VCF") (class "Default")
      (node (ref "RB2") (pin "2") (pinfunction "2_2") (pintype "passive"))
      (node (ref "RC4") (pin "1") (pinfunction "1_1") (pintype "passive"))
      (node (ref "RF4") (pin "1") (pinfunction "1_1") (pintype "passive"))
      (node (ref "VCF") (pin "18") (pinfunction "IN_18") (pintype "bidirectional"))
    )
    (net (code "72") (name "INPUT_CURRENT_SUM_STG") (class "Default")
      (node (ref "JP1") (pin "1") (pinfunction "1_1") (pintype "passive"))
      (node (ref "JP1") (pin "2") (pinfunction "2_2") (pintype "passive"))
      (node (ref "OPAMP_SUM_STG") (pin "2") (pinfunction "-IN_2") (pintype "input"))
      (node (ref "SUM_STG_C") (pin "2") (pinfunction "2_2") (pintype "passive"))
      (node (ref "SUM_STG_HEADER") (pin "1") (pinfunction "1_1") (pintype "passive"))
      (node (ref "SUM_STG_HEADER") (pin "2") (pinfunction "2_2") (pintype "passive"))
      (node (ref "SUM_STG_HEADER") (pin "3") (pinfunction "3_3") (pintype "passive"))
      (node (ref "SUM_STG_HEADER") (pin "4") (pinfunction "4_4") (pintype "passive"))
      (node (ref "SUM_STG_HEADER") (pin "5") (pinfunction "5_5") (pintype "passive"))
      (node (ref "SUM_STG_HEADER") (pin "6") (pinfunction "6_6") (pintype "passive"))
      (node (ref "SUM_STG_HEADER") (pin "7") (pinfunction "7_7") (pintype "passive"))
      (node (ref "SUM_STG_HEADER") (pin "8") (pinfunction "8_8") (pintype "passive"))
      (node (ref "SUM_STG_R") (pin "2") (pinfunction "2_2") (pintype "passive"))
      (node (ref "VCA") (pin "5") (pinfunction "OUT_5") (pintype "output"))
    )
    (net (code "73") (name "INPUT_FM_3340") (class "Default")
      (node (ref "JP_OUT_VCO3340A1") (pin "2") (pinfunction "2_2") (pintype "passive"))
      (node (ref "RTEST_13700FREQ2") (pin "1") (pinfunction "1_1") (pintype "passive"))
    )
    (net (code "74") (name "IN_4THORDER") (class "Default")
      (node (ref "IC1") (pin "26") (pinfunction "GPA5_26") (pintype "bidirectional"))
    )
    (net (code "75") (name "IN_VCA") (class "Default")
      (node (ref "R1_VCA") (pin "1") (pinfunction "1_1") (pintype "passive"))
      (node (ref "VCF_JUMPER") (pin "2") (pinfunction "2_2") (pintype "passive"))
    )
    (net (code "76") (name "IN_VCF") (class "Default")
      (node (ref "C_IN2") (pin "2") (pinfunction "2_2") (pintype "passive"))
      (node (ref "VCF_JUMPER") (pin "4") (pinfunction "4_4") (pintype "passive"))
    )
    (net (code "77") (name "IN_VCFORDER") (class "Default")
      (node (ref "R_PD_4TH_ORDER_VCF") (pin "2") (pinfunction "2_2") (pintype "passive"))
      (node (ref "VCF_ANALOG_SW") (pin "1") (pinfunction "IN_1") (pintype "input"))
      (node (ref "VCF_ANALOG_SW") (pin "16") (pinfunction "IN_16") (pintype "input"))
    )
    (net (code "78") (name "JACK_SUM_STG") (class "Default")
      (node (ref "COUT_SUM_STG") (pin "-") (pinfunction "-_-") (pintype "passive"))
      (node (ref "OUT") (pin "1") (pinfunction "1_1") (pintype "passive"))
    )
    (net (code "79") (name "LINEAR_CTRL_VCOA") (class "Default")
      (node (ref "3340A") (pin "13") (pinfunction "LINEAR_CTRL_13") (pintype "bidirectional"))
      (node (ref "R10_3") (pin "1") (pinfunction "1_1") (pintype "passive"))
      (node (ref "R8_3") (pin "1") (pinfunction "1_1") (pintype "passive"))
    )
    (net (code "80") (name "LINEAR_CTRL_VCOB") (class "Default")
      (node (ref "3340B") (pin "13") (pinfunction "LINEAR_CTRL_13") (pintype "bidirectional"))
      (node (ref "R10_1") (pin "1") (pinfunction "1_1") (pintype "passive"))
      (node (ref "R8_1") (pin "1") (pinfunction "1_1") (pintype "passive"))
    )
    (net (code "81") (name "N$4") (class "Default")
      (node (ref "JP_MIXER_A") (pin "4") (pinfunction "4_4") (pintype "passive"))
      (node (ref "MIXER_A") (pin "4") (pinfunction "I_OUT_4") (pintype "bidirectional"))
    )
    (net (code "82") (name "Net-(3A-D)") (class "Default")
      (node (ref "3") (pin "2") (pinfunction "D_2") (pintype "passive"))
      (node (ref "C1_1") (pin "2") (pinfunction "2_2") (pintype "passive"))
      (node (ref "R1_7") (pin "2") (pinfunction "2_2") (pintype "passive"))
    )
    (net (code "83") (name "Net-(3C-D)") (class "Default")
      (node (ref "3") (pin "10") (pinfunction "D_10") (pintype "passive"))
      (node (ref "C3_1") (pin "2") (pinfunction "2_2") (pintype "passive"))
      (node (ref "R3_4") (pin "2") (pinfunction "2_2") (pintype "passive"))
    )
    (net (code "84") (name "Net-(3D-D)") (class "Default")
      (node (ref "3") (pin "7") (pinfunction "D_7") (pintype "passive"))
      (node (ref "C2_1") (pin "2") (pinfunction "2_2") (pintype "passive"))
      (node (ref "R2_7") (pin "2") (pinfunction "2_2") (pintype "passive"))
    )
    (net (code "85") (name "Net-(3D-S)") (class "Default")
      (node (ref "3") (pin "6") (pinfunction "S_6") (pintype "passive"))
      (node (ref "R2S_1") (pin "2") (pinfunction "2_2") (pintype "passive"))
    )
    (net (code "86") (name "Net-(C1_SYNC1-Pad1)") (class "Default")
      (node (ref "C1_SYNC1") (pin "1") (pinfunction "1_1") (pintype "passive"))
      (node (ref "R_SYNC1") (pin "2") (pinfunction "2_2") (pintype "passive"))
    )
    (net (code "87") (name "Net-(C2_VCA-Pad2)") (class "Default")
      (node (ref "C2_VCA") (pin "2") (pinfunction "2_2") (pintype "passive"))
      (node (ref "R1_VCA") (pin "2") (pinfunction "2_2") (pintype "passive"))
      (node (ref "R2_VCA") (pin "2") (pinfunction "2_2") (pintype "passive"))
    )
    (net (code "88") (name "Net-(C4_1-Pad1)") (class "Default")
      (node (ref "C4_1") (pin "1") (pinfunction "1_1") (pintype "passive"))
      (node (ref "R10_1") (pin "2") (pinfunction "2_2") (pintype "passive"))
    )
    (net (code "89") (name "Net-(C4_3-Pad1)") (class "Default")
      (node (ref "C4_3") (pin "1") (pinfunction "1_1") (pintype "passive"))
      (node (ref "R10_3") (pin "2") (pinfunction "2_2") (pintype "passive"))
    )
    (net (code "90") (name "Net-(CIN1_MIXERA-Pad2)") (class "Default")
      (node (ref "CIN1_MIXERA") (pin "2") (pinfunction "2_2") (pintype "passive"))
      (node (ref "RIN1_MIXERA") (pin "2") (pinfunction "2_2") (pintype "passive"))
    )
    (net (code "91") (name "Net-(CIN2_MIXERA-Pad2)") (class "Default")
      (node (ref "CIN2_MIXERA") (pin "2") (pinfunction "2_2") (pintype "passive"))
      (node (ref "RIN2_MIXERA") (pin "2") (pinfunction "2_2") (pintype "passive"))
    )
    (net (code "92") (name "Net-(CIN2_MIXERB-Pad2)") (class "Default")
      (node (ref "CIN2_MIXERB") (pin "2") (pinfunction "2_2") (pintype "passive"))
      (node (ref "RIN2_MIXERB") (pin "2") (pinfunction "2_2") (pintype "passive"))
    )
    (net (code "93") (name "Net-(CIN3_MIXERA-Pad2)") (class "Default")
      (node (ref "CIN3_MIXERA") (pin "2") (pinfunction "2_2") (pintype "passive"))
      (node (ref "RIN3_MIXERA") (pin "2") (pinfunction "2_2") (pintype "passive"))
    )
    (net (code "94") (name "Net-(CIN3_MIXERB-Pad2)") (class "Default")
      (node (ref "CIN3_MIXERB") (pin "2") (pinfunction "2_2") (pintype "passive"))
      (node (ref "RIN3_MIXERB") (pin "2") (pinfunction "2_2") (pintype "passive"))
    )
    (net (code "95") (name "Net-(CIN4_MIXERA-Pad2)") (class "Default")
      (node (ref "CIN4_MIXERA") (pin "2") (pinfunction "2_2") (pintype "passive"))
      (node (ref "RIN4_MIXERA") (pin "2") (pinfunction "2_2") (pintype "passive"))
    )
    (net (code "96") (name "Net-(CIN4_MIXERB-Pad2)") (class "Default")
      (node (ref "CIN4_MIXERB") (pin "2") (pinfunction "2_2") (pintype "passive"))
      (node (ref "RIN4_MIXERB") (pin "2") (pinfunction "2_2") (pintype "passive"))
    )
    (net (code "97") (name "Net-(CIN4_MIXERB1-Pad1)") (class "Default")
      (node (ref "CIN4_MIXERB1") (pin "1") (pinfunction "1_1") (pintype "passive"))
      (node (ref "JP_OUT_VCO3340A2") (pin "2") (pinfunction "2_2") (pintype "passive"))
    )
    (net (code "98") (name "Net-(CIN4_MIXERB1-Pad2)") (class "Default")
      (node (ref "CIN4_MIXERB1") (pin "2") (pinfunction "2_2") (pintype "passive"))
      (node (ref "RIN4_MIXERB1") (pin "2") (pinfunction "2_2") (pintype "passive"))
    )
    (net (code "99") (name "Net-(CONVLOG2-C1)") (class "Default")
      (node (ref "CONVLOG2") (pin "6") (pinfunction "C1_6") (pintype "passive"))
      (node (ref "EXPCONV2") (pin "2") (pinfunction "-IN_2") (pintype "input"))
      (node (ref "RBIAS_EXPCONV2") (pin "2") (pinfunction "2_2") (pintype "passive"))
    )
    (net (code "100") (name "Net-(CONVLOG2-E1)") (class "Default")
      (node (ref "CONVLOG2") (pin "1") (pinfunction "E1_1") (pintype "passive"))
      (node (ref "CONVLOG2") (pin "4") (pinfunction "E2_4") (pintype "passive"))
      (node (ref "R5_EXPCONV2") (pin "1") (pinfunction "1_1") (pintype "passive"))
    )
    (net (code "101") (name "Net-(CONV_ITOV_OUT--IN)") (class "Default")
      (node (ref "CONV_ITOV_OUT") (pin "2") (pinfunction "-IN_2") (pintype "input"))
      (node (ref "C_CONV_ITOV_OUT") (pin "1") (pinfunction "1_1") (pintype "passive"))
      (node (ref "JP_MIXER_A") (pin "1") (pinfunction "1_1") (pintype "passive"))
      (node (ref "JP_MIXER_A") (pin "3") (pinfunction "3_3") (pintype "passive"))
      (node (ref "JP_MIXER_A") (pin "5") (pinfunction "5_5") (pintype "passive"))
      (node (ref "JP_MIXER_A") (pin "7") (pinfunction "7_7") (pintype "passive"))
      (node (ref "JP_MIXER_B") (pin "1") (pinfunction "1_1") (pintype "passive"))
      (node (ref "JP_MIXER_B") (pin "3") (pinfunction "3_3") (pintype "passive"))
      (node (ref "JP_MIXER_B") (pin "5") (pinfunction "5_5") (pintype "passive"))
      (node (ref "JP_MIXER_B") (pin "7") (pinfunction "7_7") (pintype "passive"))
      (node (ref "R_CONV_ITOV_OUT") (pin "1") (pinfunction "1_1") (pintype "passive"))
    )
    (net (code "102") (name "Net-(CSTAB1_MIXERA-Pad2)") (class "Default")
      (node (ref "CSTAB1_MIXERA") (pin "2") (pinfunction "2_2") (pintype "passive"))
      (node (ref "RSTAB1_MIXERA") (pin "2") (pinfunction "2_2") (pintype "passive"))
    )
    (net (code "103") (name "Net-(CSTAB2-Pad1)") (class "Default")
      (node (ref "CSTAB2") (pin "1") (pinfunction "1_1") (pintype "passive"))
      (node (ref "JP_OUT_VCO3340A1") (pin "1") (pinfunction "1_1") (pintype "passive"))
    )
    (net (code "104") (name "Net-(CSTAB2_MIXERA-Pad2)") (class "Default")
      (node (ref "CSTAB2_MIXERA") (pin "2") (pinfunction "2_2") (pintype "passive"))
      (node (ref "RSTAB2_MIXERA") (pin "2") (pinfunction "2_2") (pintype "passive"))
    )
    (net (code "105") (name "Net-(CSTAB2_MIXERB-Pad2)") (class "Default")
      (node (ref "CSTAB2_MIXERB") (pin "2") (pinfunction "2_2") (pintype "passive"))
      (node (ref "RSTAB2_MIXERB") (pin "2") (pinfunction "2_2") (pintype "passive"))
    )
    (net (code "106") (name "Net-(CSTAB3-Pad2)") (class "Default")
      (node (ref "CSTAB3") (pin "2") (pinfunction "2_2") (pintype "passive"))
      (node (ref "RSTAB4_MIXERB2") (pin "2") (pinfunction "2_2") (pintype "passive"))
    )
    (net (code "107") (name "Net-(CSTAB3_MIXERA-Pad2)") (class "Default")
      (node (ref "CSTAB3_MIXERA") (pin "2") (pinfunction "2_2") (pintype "passive"))
      (node (ref "RSTAB3_MIXERA") (pin "2") (pinfunction "2_2") (pintype "passive"))
    )
    (net (code "108") (name "Net-(CSTAB3_MIXERB-Pad2)") (class "Default")
      (node (ref "CSTAB3_MIXERB") (pin "2") (pinfunction "2_2") (pintype "passive"))
      (node (ref "RSTAB3_MIXERB") (pin "2") (pinfunction "2_2") (pintype "passive"))
    )
    (net (code "109") (name "Net-(CSTAB4_MIXERA-Pad2)") (class "Default")
      (node (ref "CSTAB4_MIXERA") (pin "2") (pinfunction "2_2") (pintype "passive"))
      (node (ref "RSTAB4_MIXERA") (pin "2") (pinfunction "2_2") (pintype "passive"))
    )
    (net (code "110") (name "Net-(CSTAB8-Pad2)") (class "Default")
      (node (ref "CSTAB8") (pin "2") (pinfunction "2_2") (pintype "passive"))
      (node (ref "RSTAB4_MIXERB") (pin "2") (pinfunction "2_2") (pintype "passive"))
    )
    (net (code "111") (name "Net-(C_CV_FREQ_STAB1-Pad2)") (class "Default")
      (node (ref "C_CV_FREQ_STAB1") (pin "2") (pinfunction "2_2") (pintype "passive"))
      (node (ref "R_CV_FREQ_STAB1") (pin "2") (pinfunction "2_2") (pintype "passive"))
    )
    (net (code "112") (name "Net-(C_CV_FREQ_STAB3-Pad2)") (class "Default")
      (node (ref "C_CV_FREQ_STAB3") (pin "2") (pinfunction "2_2") (pintype "passive"))
      (node (ref "R_CV_FREQ_STAB3") (pin "2") (pinfunction "2_2") (pintype "passive"))
    )
    (net (code "113") (name "Net-(C_IN2-Pad1)") (class "Default")
      (node (ref "C_IN2") (pin "1") (pinfunction "1_1") (pintype "passive"))
      (node (ref "RC1_VCF") (pin "1") (pinfunction "1_1") (pintype "passive"))
    )
    (net (code "114") (name "Net-(D_2-PadC)") (class "Default")
      (node (ref "D_2") (pin "C") (pinfunction "C_C") (pintype "passive"))
      (node (ref "R_LIM_2") (pin "2") (pinfunction "2_2") (pintype "passive"))
    )
    (net (code "115") (name "Net-(EXPCONV2-OUT)") (class "Default")
      (node (ref "EXPCONV2") (pin "6") (pinfunction "OUT_6") (pintype "output"))
      (node (ref "R5_EXPCONV2") (pin "2") (pinfunction "2_2") (pintype "passive"))
    )
    (net (code "116") (name "Net-(HEADER_EXPCONV2-Pad1)") (class "Default")
      (node (ref "HEADER_EXPCONV2") (pin "1") (pinfunction "1_1") (pintype "passive"))
      (node (ref "RTEST_LOG2") (pin "1") (pinfunction "1_1") (pintype "passive"))
    )
    (net (code "117") (name "Net-(MIXER_BB-I_IN)") (class "Default")
      (node (ref "MIXER_B") (pin "2") (pinfunction "I_IN_2") (pintype "bidirectional"))
      (node (ref "RIN4_MIXERB1") (pin "1") (pinfunction "1_1") (pintype "passive"))
      (node (ref "RSTAB4_MIXERB2") (pin "1") (pinfunction "1_1") (pintype "passive"))
    )
    (net (code "118") (name "Net-(MIXER_BB-I_OUT)") (class "Default")
      (node (ref "CSTAB2") (pin "2") (pinfunction "2_2") (pintype "passive"))
      (node (ref "MIXER_B") (pin "4") (pinfunction "I_OUT_4") (pintype "bidirectional"))
      (node (ref "RSTAB4_MIXERB1") (pin "2") (pinfunction "2_2") (pintype "passive"))
    )
    (net (code "119") (name "Net-(MIXER_BE-I_OUT)") (class "Default")
      (node (ref "JP_MIXER_B") (pin "8") (pinfunction "8_8") (pintype "passive"))
      (node (ref "MIXER_B") (pin "12") (pinfunction "I_OUT_12") (pintype "bidirectional"))
    )
    (net (code "120") (name "Net-(S1-P)") (class "Default")
      (node (ref "R_SW1A") (pin "2") (pinfunction "2_2") (pintype "passive"))
      (node (ref "R_SW1B") (pin "1") (pinfunction "1_1") (pintype "passive"))
      (node (ref "S1") (pin "3") (pinfunction "P_3") (pintype "passive"))
      (node (ref "S1") (pin "4") (pinfunction "P1_4") (pintype "passive"))
    )
    (net (code "121") (name "Net-(S2-P)") (class "Default")
      (node (ref "R_SW2A") (pin "2") (pinfunction "2_2") (pintype "passive"))
      (node (ref "R_SW2B") (pin "1") (pinfunction "1_1") (pintype "passive"))
      (node (ref "S2") (pin "3") (pinfunction "P_3") (pintype "passive"))
      (node (ref "S2") (pin "4") (pinfunction "P1_4") (pintype "passive"))
    )
    (net (code "122") (name "Net-(SUBBASS2-1J)") (class "Default")
      (node (ref "SUBBASS2") (pin "10") (pinfunction "1J_10") (pintype "input"))
      (node (ref "SUBBASS2") (pin "14") (pinfunction "1~{Q}_14") (pintype "output"))
    )
    (net (code "123") (name "Net-(VCAC-IN_N)") (class "Default")
      (node (ref "R5_VCA") (pin "2") (pinfunction "2_2") (pintype "passive"))
      (node (ref "VCA") (pin "4") (pinfunction "IN_N_4") (pintype "input"))
    )
    (net (code "124") (name "Net-(VCAC-I_BIAS)") (class "Default")
      (node (ref "R_GAIN_VCA") (pin "2") (pinfunction "2_2") (pintype "passive"))
      (node (ref "VCA") (pin "1") (pinfunction "I_BIAS_1") (pintype "input"))
    )
    (net (code "125") (name "Net-(VCF_ANALOG_SWA-S)") (class "Default")
      (node (ref "CRES_VCF") (pin "1") (pinfunction "1_1") (pintype "passive"))
      (node (ref "VCF_ANALOG_SW") (pin "14") (pinfunction "S_14") (pintype "bidirectional"))
      (node (ref "VCF_ANALOG_SW") (pin "3") (pinfunction "S_3") (pintype "bidirectional"))
    )
    (net (code "126") (name "Net-(VCO2A-B)") (class "Default")
      (node (ref "CF_2") (pin "2") (pinfunction "2_2") (pintype "passive"))
      (node (ref "VCO2") (pin "5") (pinfunction "OUT_5") (pintype "output"))
      (node (ref "VCO2") (pin "7") (pinfunction "B_7") (pintype "passive"))
    )
    (net (code "127") (name "Net-(VCO2B-B)") (class "Default")
      (node (ref "RA_2") (pin "2") (pinfunction "2_2") (pintype "passive"))
      (node (ref "VCO2") (pin "10") (pinfunction "B_10") (pintype "passive"))
      (node (ref "VCO2") (pin "12") (pinfunction "OUT_12") (pintype "output"))
      (node (ref "VCO2") (pin "14") (pinfunction "IN_P_14") (pintype "input"))
      (node (ref "VCO2") (pin "3") (pinfunction "IN_P_3") (pintype "input"))
    )
    (net (code "128") (name "OUT1_VCF") (class "Default")
      (node (ref "RC2_VCF") (pin "2") (pinfunction "2_2") (pintype "passive"))
      (node (ref "RF1_VCF") (pin "1") (pinfunction "1_1") (pintype "passive"))
      (node (ref "VCF") (pin "7") (pinfunction "OUT_7") (pintype "bidirectional"))
    )
    (net (code "129") (name "OUT2_VCF") (class "Default")
      (node (ref "RC3") (pin "2") (pinfunction "2_2") (pintype "passive"))
      (node (ref "RF2_VCF") (pin "2") (pinfunction "2_2") (pintype "passive"))
      (node (ref "VCF") (pin "6") (pinfunction "OUT_6") (pintype "bidirectional"))
      (node (ref "VCF_ANALOG_SW") (pin "15") (pinfunction "D_15") (pintype "bidirectional"))
    )
    (net (code "130") (name "OUT3_VCF") (class "Default")
      (node (ref "RC4") (pin "2") (pinfunction "2_2") (pintype "passive"))
      (node (ref "RF3") (pin "2") (pinfunction "2_2") (pintype "passive"))
      (node (ref "VCF") (pin "15") (pinfunction "OUT_15") (pintype "bidirectional"))
    )
    (net (code "131") (name "OUT4_VCF") (class "Default")
      (node (ref "RF4") (pin "2") (pinfunction "2_2") (pintype "passive"))
      (node (ref "VCF") (pin "10") (pinfunction "OUT_10") (pintype "bidirectional"))
      (node (ref "VCF_ANALOG_SW") (pin "2") (pinfunction "D_2") (pintype "bidirectional"))
    )
    (net (code "132") (name "OUT_EXPCONV_VCO13700") (class "Default")
      (node (ref "CONVLOG2") (pin "3") (pinfunction "C2_3") (pintype "passive"))
      (node (ref "HEADER_EXPCONV2") (pin "2") (pinfunction "2_2") (pintype "passive"))
    )
    (net (code "133") (name "OUT_MIXER") (class "Default")
      (node (ref "CONV_ITOV_OUT") (pin "6") (pinfunction "OUT_6") (pintype "output"))
      (node (ref "C_CONV_ITOV_OUT") (pin "2") (pinfunction "2_2") (pintype "passive"))
      (node (ref "R_CONV_ITOV_OUT") (pin "2") (pinfunction "2_2") (pintype "passive"))
      (node (ref "VCF_JUMPER") (pin "3") (pinfunction "3_3") (pintype "passive"))
    )
    (net (code "134") (name "OUT_SUM_STG") (class "Default")
      (node (ref "OPAMP_SUM_STG") (pin "6") (pinfunction "OUT_6") (pintype "output"))
      (node (ref "ROUT_SUM_STG") (pin "2") (pinfunction "2_2") (pintype "passive"))
      (node (ref "SUM_STG_C") (pin "1") (pinfunction "1_1") (pintype "passive"))
      (node (ref "SUM_STG_R") (pin "1") (pinfunction "1_1") (pintype "passive"))
    )
    (net (code "135") (name "OUT_VCF") (class "Default")
      (node (ref "CRES_VCF") (pin "2") (pinfunction "2_2") (pintype "passive"))
      (node (ref "RRI_VCF") (pin "2") (pinfunction "2_2") (pintype "passive"))
      (node (ref "VCF_JUMPER") (pin "1") (pinfunction "1_1") (pintype "passive"))
    )
    (net (code "136") (name "PNP1_B_VCO13700") (class "Default")
      (node (ref "CONVLOG2") (pin "2") (pinfunction "B1_2") (pintype "passive"))
      (node (ref "R1_EXPCONV2") (pin "1") (pinfunction "1_1") (pintype "passive"))
      (node (ref "R2_EXPCONV2") (pin "1") (pinfunction "1_1") (pintype "passive"))
    )
    (net (code "137") (name "PNP2_B_VCO13700") (class "Default")
      (node (ref "CONVLOG2") (pin "5") (pinfunction "B2_5") (pintype "passive"))
      (node (ref "R3_EXPCONV2") (pin "1") (pinfunction "1_1") (pintype "passive"))
      (node (ref "R4_EXPCONV2") (pin "1") (pinfunction "1_1") (pintype "passive"))
    )
    (net (code "138") (name "POT2_SUM_STG") (class "Default")
      (node (ref "COUT_SUM_STG") (pin "+") (pinfunction "+_+") (pintype "passive"))
      (node (ref "POT_SUM_STG") (pin "2") (pinfunction "S_2") (pintype "passive"))
    )
    (net (code "139") (name "POT3_SUM_STG") (class "Default")
      (node (ref "POT_SUM_STG") (pin "3") (pinfunction "E_3") (pintype "passive"))
      (node (ref "ROUT_SUM_STG") (pin "1") (pinfunction "1_1") (pintype "passive"))
    )
    (net (code "140") (name "PULSE_OUT_VCOA") (class "Default")
      (node (ref "3") (pin "11") (pinfunction "S_11") (pintype "passive"))
      (node (ref "R3S_1") (pin "2") (pinfunction "2_2") (pintype "passive"))
    )
    (net (code "141") (name "PULSE_VCOA") (class "Default")
      (node (ref "3340A") (pin "4") (pinfunction "PULSE_OUT_4") (pintype "bidirectional"))
      (node (ref "C3_1") (pin "1") (pinfunction "1_1") (pintype "passive"))
      (node (ref "R6_3") (pin "2") (pinfunction "2_2") (pintype "passive"))
      (node (ref "TP_PULSE3") (pin "P$1") (pinfunction "P$1_P$1") (pintype "passive"))
    )
    (net (code "142") (name "REFOUT") (class "Default")
      (node (ref "CDEC_VREF") (pin "1") (pinfunction "1_1") (pintype "passive"))
      (node (ref "U1") (pin "5") (pinfunction "REFOUT/REFIN_5") (pintype "bidirectional"))
    )
    (net (code "143") (name "RES_CUR_IN_VCF") (class "Default")
      (node (ref "RRI_VCF") (pin "1") (pinfunction "1_1") (pintype "passive"))
      (node (ref "VCF") (pin "8") (pinfunction "IN_RES_8") (pintype "bidirectional"))
    )
    (net (code "144") (name "RES_CUR_VCF") (class "Default")
      (node (ref "R_RES_VCF") (pin "1") (pinfunction "1_1") (pintype "passive"))
      (node (ref "VCF") (pin "9") (pinfunction "RES_CUR_9") (pintype "bidirectional"))
    )
    (net (code "145") (name "RST") (class "Default")
      (node (ref "IC1") (pin "18") (pinfunction "~{RESET}_18") (pintype "input"))
      (node (ref "R_RST") (pin "2") (pinfunction "2_2") (pintype "passive"))
      (node (ref "STM32L432KC_CONN_") (pin "3.6") (pinfunction "PB0_3.6") (pintype "bidirectional"))
      (node (ref "U1") (pin "37") (pinfunction "~{RESET}_37") (pintype "input"))
    )
    (net (code "146") (name "SAW_3340_VCOA") (class "Default")
      (node (ref "C2_1") (pin "1") (pinfunction "1_1") (pintype "passive"))
      (node (ref "R7_3") (pin "1") (pinfunction "1_1") (pintype "passive"))
      (node (ref "TP_SAW3") (pin "P$1") (pinfunction "P$1_P$1") (pintype "passive"))
    )
    (net (code "147") (name "SAW_VCOA") (class "Default")
      (node (ref "3340A") (pin "8") (pinfunction "SAW_OUT_8") (pintype "bidirectional"))
      (node (ref "R7_3") (pin "2") (pinfunction "2_2") (pintype "passive"))
    )
    (net (code "148") (name "SAW_VCOB") (class "Default")
      (node (ref "3340B") (pin "8") (pinfunction "SAW_OUT_8") (pintype "bidirectional"))
      (node (ref "R7_1") (pin "2") (pinfunction "2_2") (pintype "passive"))
    )
    (net (code "149") (name "SCALE_VCOA") (class "Default")
      (node (ref "3340A") (pin "14") (pinfunction "SCALE_14") (pintype "bidirectional"))
      (node (ref "R11_3") (pin "1") (pinfunction "1_1") (pintype "passive"))
    )
    (net (code "150") (name "SCALE_VCOB") (class "Default")
      (node (ref "3340B") (pin "14") (pinfunction "SCALE_14") (pintype "bidirectional"))
      (node (ref "R11_1") (pin "1") (pinfunction "1_1") (pintype "passive"))
    )
    (net (code "151") (name "SCL") (class "Default")
      (node (ref "IC1") (pin "12") (pinfunction "SCL_12") (pintype "input"))
      (node (ref "IC_EEPROM") (pin "6") (pinfunction "SCL_6") (pintype "input"))
      (node (ref "STM32L432KC_CONN_") (pin "4.6") (pinfunction "PA7_4.6") (pintype "bidirectional"))
    )
    (net (code "152") (name "SDA") (class "Default")
      (node (ref "IC1") (pin "13") (pinfunction "SDA_13") (pintype "bidirectional"))
      (node (ref "IC_EEPROM") (pin "5") (pinfunction "SDA_5") (pintype "bidirectional"))
      (node (ref "STM32L432KC_CONN_") (pin "3.15") (pinfunction "PB4_3.15") (pintype "bidirectional"))
    )
    (net (code "153") (name "SOFT_SYNC_VCOA") (class "Default")
      (node (ref "3340A") (pin "9") (pinfunction "SOFT_SYNC_9") (pintype "bidirectional"))
      (node (ref "C2_SYNC3") (pin "2") (pinfunction "2_2") (pintype "passive"))
    )
    (net (code "154") (name "SOFT_SYNC_VCOB") (class "Default")
      (node (ref "3340B") (pin "9") (pinfunction "SOFT_SYNC_9") (pintype "bidirectional"))
      (node (ref "C2_SYNC1") (pin "2") (pinfunction "2_2") (pintype "passive"))
    )
    (net (code "155") (name "SPI_CLK") (class "Default")
      (node (ref "STM32L432KC_CONN_") (pin "4.11") (pinfunction "PA1_4.11") (pintype "bidirectional"))
      (node (ref "U1") (pin "49") (pinfunction "SCLK/SCL_49") (pintype "input"))
    )
    (net (code "156") (name "SPI_MISO") (class "Default")
      (node (ref "STM32L432KC_CONN_") (pin "4.7") (pinfunction "PA6_4.7") (pintype "bidirectional"))
      (node (ref "U1") (pin "48") (pinfunction "SDO_48") (pintype "tri_state"))
    )
    (net (code "157") (name "SPI_MOSI") (class "Default")
      (node (ref "STM32L432KC_CONN_") (pin "3.5") (pinfunction "PA12_3.5") (pintype "bidirectional"))
      (node (ref "U1") (pin "50") (pinfunction "DIN/SDA_50") (pintype "bidirectional"))
    )
    (net (code "158") (name "SUBBASS_IN_VCO13700") (class "Default")
      (node (ref "R_LIM_2") (pin "1") (pinfunction "1_1") (pintype "passive"))
      (node (ref "SUBBASS2") (pin "13") (pinfunction "1CP_13") (pintype "input"))
    )
    (net (code "159") (name "SW1") (class "Default")
      (node (ref "C_SW1") (pin "1") (pinfunction "1_1") (pintype "passive"))
      (node (ref "R_SW1B") (pin "2") (pinfunction "2_2") (pintype "passive"))
      (node (ref "STM32L432KC_CONN_") (pin "3.14") (pinfunction "PB5_3.14") (pintype "bidirectional"))
    )
    (net (code "160") (name "SW2") (class "Default")
      (node (ref "C_SW2") (pin "1") (pinfunction "1_1") (pintype "passive"))
      (node (ref "R_SW2B") (pin "2") (pinfunction "2_2") (pintype "passive"))
      (node (ref "STM32L432KC_CONN_") (pin "3.13") (pinfunction "PA11_3.13") (pintype "bidirectional"))
    )
    (net (code "161") (name "SYNC_3340_VCOA") (class "Default")
      (node (ref "3") (pin "15") (pinfunction "D_15") (pintype "passive"))
      (node (ref "C1_SYNC3") (pin "1") (pinfunction "1_1") (pintype "passive"))
      (node (ref "R_SYNC3") (pin "2") (pinfunction "2_2") (pintype "passive"))
    )
    (net (code "162") (name "SYNC_IN_VCOA") (class "Default")
      (node (ref "3") (pin "14") (pinfunction "S_14") (pintype "passive"))
      (node (ref "JP_SYNC_3340B_TO_A") (pin "1") (pinfunction "1_1") (pintype "passive"))
    )
    (net (code "163") (name "TEMPCO1_VCOA") (class "Default")
      (node (ref "3340A") (pin "1") (pinfunction "MUL_GAIN1_1") (pintype "bidirectional"))
      (node (ref "R1_4") (pin "1") (pinfunction "1_1") (pintype "passive"))
    )
    (net (code "164") (name "TEMPCO1_VCOB") (class "Default")
      (node (ref "3340B") (pin "1") (pinfunction "MUL_GAIN1_1") (pintype "bidirectional"))
      (node (ref "R1_3") (pin "1") (pinfunction "1_1") (pintype "passive"))
    )
    (net (code "165") (name "TEMPCO2_VCOA") (class "Default")
      (node (ref "3340A") (pin "2") (pinfunction "MUL_GAIN2_2") (pintype "bidirectional"))
      (node (ref "R2_4") (pin "1") (pinfunction "1_1") (pintype "passive"))
    )
    (net (code "166") (name "TEMPCO2_VCOB") (class "Default")
      (node (ref "3340B") (pin "2") (pinfunction "MUL_GAIN2_2") (pintype "bidirectional"))
      (node (ref "R2_3") (pin "1") (pinfunction "1_1") (pintype "passive"))
    )
    (net (code "167") (name "TIMING_CAP_VCOA") (class "Default")
      (node (ref "3340A") (pin "11") (pinfunction "TIMING_CAP_11") (pintype "bidirectional"))
      (node (ref "C_3") (pin "2") (pinfunction "2_2") (pintype "passive"))
    )
    (net (code "168") (name "TIMING_CAP_VCOB") (class "Default")
      (node (ref "3340B") (pin "11") (pinfunction "TIMING_CAP_11") (pintype "bidirectional"))
      (node (ref "C_1") (pin "2") (pinfunction "2_2") (pintype "passive"))
    )
    (net (code "169") (name "TRI_3340_VCOA") (class "Default")
      (node (ref "3340A") (pin "10") (pinfunction "TRI_OUT_10") (pintype "bidirectional"))
      (node (ref "C1_1") (pin "1") (pinfunction "1_1") (pintype "passive"))
      (node (ref "TP_TRI3") (pin "P$1") (pinfunction "P$1_P$1") (pintype "passive"))
    )
    (net (code "170") (name "TRI_OUT_VCOA") (class "Default")
      (node (ref "3") (pin "3") (pinfunction "S_3") (pintype "passive"))
      (node (ref "R1S_1") (pin "1") (pinfunction "1_1") (pintype "passive"))
    )
    (net (code "171") (name "USART_RX_RPI_TX") (class "Default")
      (node (ref "CONN_UART_RPI") (pin "2") (pinfunction "2_2") (pintype "passive"))
      (node (ref "STM32L432KC_CONN_") (pin "3.7") (pinfunction "PB7_3.7") (pintype "bidirectional"))
    )
    (net (code "172") (name "USART_TX_RPI_RX") (class "Default")
      (node (ref "CONN_UART_RPI") (pin "3") (pinfunction "3_3") (pintype "passive"))
      (node (ref "STM32L432KC_CONN_") (pin "3.8") (pinfunction "PB6_3.8") (pintype "bidirectional"))
    )
    (net (code "173") (name "VCO440A_OUT") (class "Default")
      (node (ref "JP_OUT_VCO3340A") (pin "1") (pinfunction "1_1") (pintype "passive"))
      (node (ref "R1S_1") (pin "2") (pinfunction "2_2") (pintype "passive"))
      (node (ref "R2S_1") (pin "1") (pinfunction "1_1") (pintype "passive"))
      (node (ref "R3S_1") (pin "1") (pinfunction "1_1") (pintype "passive"))
    )
    (net (code "174") (name "VCO3340B_PULSE_OUT") (class "Default")
      (node (ref "3340B") (pin "4") (pinfunction "PULSE_OUT_4") (pintype "bidirectional"))
      (node (ref "JP_PULSEOUT_VCO3340B") (pin "1") (pinfunction "1_1") (pintype "passive"))
      (node (ref "R6_1") (pin "2") (pinfunction "2_2") (pintype "passive"))
      (node (ref "TP_PULSE1") (pin "P$1") (pinfunction "P$1_P$1") (pintype "passive"))
    )
    (net (code "175") (name "VCO3340B_SAW_OUT") (class "Default")
      (node (ref "JP_SAWOUT_VCO3340B") (pin "1") (pinfunction "1_1") (pintype "passive"))
      (node (ref "JP_SYNC_3340B_TO_A") (pin "2") (pinfunction "2_2") (pintype "passive"))
      (node (ref "R7_1") (pin "1") (pinfunction "1_1") (pintype "passive"))
      (node (ref "TP_SAW1") (pin "P$1") (pinfunction "P$1_P$1") (pintype "passive"))
    )
    (net (code "176") (name "VCO3340B_TRI_OUT") (class "Default")
      (node (ref "3340B") (pin "10") (pinfunction "TRI_OUT_10") (pintype "bidirectional"))
      (node (ref "JP_TRIOUT_VCO3340B") (pin "1") (pinfunction "1_1") (pintype "passive"))
      (node (ref "TP_TRI1") (pin "P$1") (pinfunction "P$1_P$1") (pintype "passive"))
    )
    (net (code "177") (name "VCO13700_SQUARE") (class "Default")
      (node (ref "CIN_2") (pin "2") (pinfunction "2_2") (pintype "passive"))
      (node (ref "JP8") (pin "1") (pinfunction "1_1") (pintype "passive"))
      (node (ref "RSQU_2") (pin "2") (pinfunction "2_2") (pintype "passive"))
      (node (ref "TP_13700_SQU2") (pin "P$1") (pinfunction "P$1_P$1") (pintype "passive"))
      (node (ref "VCO2") (pin "9") (pinfunction "E_9") (pintype "passive"))
    )
    (net (code "178") (name "VCO13700_SUBBASS") (class "Default")
      (node (ref "JP7") (pin "1") (pinfunction "1_1") (pintype "passive"))
      (node (ref "RCAL_1") (pin "1") (pinfunction "1_1") (pintype "passive"))
      (node (ref "SUBBASS2") (pin "15") (pinfunction "1Q_15") (pintype "output"))
    )
    (net (code "179") (name "VCO13700_TRI") (class "Default")
      (node (ref "JP9") (pin "1") (pinfunction "1_1") (pintype "passive"))
      (node (ref "RTRI_2") (pin "2") (pinfunction "2_2") (pintype "passive"))
      (node (ref "TP_13700_TRI2") (pin "P$1") (pinfunction "P$1_P$1") (pintype "passive"))
      (node (ref "VCO2") (pin "13") (pinfunction "IN_N_13") (pintype "input"))
      (node (ref "VCO2") (pin "8") (pinfunction "E_8") (pintype "passive"))
    )
    (net (code "180") (name "VEE_VCF") (class "Default")
      (node (ref "C-15VPOL_VCF") (pin "1") (pinfunction "1_1") (pintype "passive"))
      (node (ref "C-15V_VCF") (pin "1") (pinfunction "1_1") (pintype "passive"))
      (node (ref "REE_VCF") (pin "2") (pinfunction "2_2") (pintype "passive"))
      (node (ref "VCF") (pin "13") (pinfunction "V-_13") (pintype "bidirectional"))
    )
    (net (code "181") (name "VEE_VCOA") (class "Default")
      (node (ref "3340A") (pin "3") (pinfunction "VEE_3") (pintype "bidirectional"))
      (node (ref "CDEC_3340B6") (pin "2") (pinfunction "2_2") (pintype "passive"))
      (node (ref "CDEC_3340B7") (pin "2") (pinfunction "2_2") (pintype "passive"))
      (node (ref "R1_4") (pin "2") (pinfunction "2_2") (pintype "passive"))
      (node (ref "R2_4") (pin "2") (pinfunction "2_2") (pintype "passive"))
      (node (ref "R3_3") (pin "2") (pinfunction "2_2") (pintype "passive"))
    )
    (net (code "182") (name "VEE_VCOB") (class "Default")
      (node (ref "3340B") (pin "3") (pinfunction "VEE_3") (pintype "bidirectional"))
      (node (ref "CDEC_3340B2") (pin "2") (pinfunction "2_2") (pintype "passive"))
      (node (ref "CDEC_3340B3") (pin "2") (pinfunction "2_2") (pintype "passive"))
      (node (ref "R1_3") (pin "2") (pinfunction "2_2") (pintype "passive"))
      (node (ref "R2_3") (pin "2") (pinfunction "2_2") (pintype "passive"))
      (node (ref "R3_1") (pin "2") (pinfunction "2_2") (pintype "passive"))
    )
    (net (code "183") (name "unconnected-(3340A-CURRENT_CORR-Pad7)") (class "Default")
      (node (ref "3340A") (pin "7") (pinfunction "CURRENT_CORR_7") (pintype "bidirectional"))
    )
    (net (code "184") (name "unconnected-(3340B-CURRENT_CORR-Pad7)") (class "Default")
      (node (ref "3340B") (pin "7") (pinfunction "CURRENT_CORR_7") (pintype "bidirectional"))
    )
    (net (code "185") (name "unconnected-(CONV_ITOV_OUT-CMP-Pad5)") (class "Default")
      (node (ref "CONV_ITOV_OUT") (pin "5") (pinfunction "CMP_5") (pintype "passive"))
    )
    (net (code "186") (name "unconnected-(CONV_ITOV_OUT-ON-Pad1)") (class "Default")
      (node (ref "CONV_ITOV_OUT") (pin "1") (pinfunction "ON_1") (pintype "passive"))
    )
    (net (code "187") (name "unconnected-(CONV_ITOV_OUT-ON{slash}CMP-Pad8)") (class "Default")
      (node (ref "CONV_ITOV_OUT") (pin "8") (pinfunction "ON/CMP_8") (pintype "passive"))
    )
    (net (code "188") (name "unconnected-(IC1-GPA4-Pad25)") (class "Default")
      (node (ref "IC1") (pin "25") (pinfunction "GPA4_25") (pintype "bidirectional"))
    )
    (net (code "189") (name "unconnected-(IC1-GPA6-Pad27)") (class "Default")
      (node (ref "IC1") (pin "27") (pinfunction "GPA6_27") (pintype "bidirectional"))
    )
    (net (code "190") (name "unconnected-(IC1-GPA7-Pad28)") (class "Default")
      (node (ref "IC1") (pin "28") (pinfunction "GPA7_28") (pintype "bidirectional"))
    )
    (net (code "191") (name "unconnected-(IC1-GPB0-Pad1)") (class "Default")
      (node (ref "IC1") (pin "1") (pinfunction "GPB0_1") (pintype "bidirectional"))
    )
    (net (code "192") (name "unconnected-(IC1-GPB1-Pad2)") (class "Default")
      (node (ref "IC1") (pin "2") (pinfunction "GPB1_2") (pintype "bidirectional"))
    )
    (net (code "193") (name "unconnected-(IC1-GPB2-Pad3)") (class "Default")
      (node (ref "IC1") (pin "3") (pinfunction "GPB2_3") (pintype "bidirectional"))
    )
    (net (code "194") (name "unconnected-(IC1-GPB3-Pad4)") (class "Default")
      (node (ref "IC1") (pin "4") (pinfunction "GPB3_4") (pintype "bidirectional"))
    )
    (net (code "195") (name "unconnected-(IC1-GPB4-Pad5)") (class "Default")
      (node (ref "IC1") (pin "5") (pinfunction "GPB4_5") (pintype "bidirectional"))
    )
    (net (code "196") (name "unconnected-(IC1-INTA-Pad20)") (class "Default")
      (node (ref "IC1") (pin "20") (pinfunction "INTA_20") (pintype "output"))
    )
    (net (code "197") (name "unconnected-(IC1-INTB-Pad19)") (class "Default")
      (node (ref "IC1") (pin "19") (pinfunction "INTB_19") (pintype "output"))
    )
    (net (code "198") (name "unconnected-(JP_FMLIN_VCO3340B1-Pad2)") (class "Default")
      (node (ref "JP_FMLIN_VCO3340B1") (pin "2") (pinfunction "2_2") (pintype "passive"))
    )
    (net (code "199") (name "unconnected-(JP_MIXER_B-Pad2)") (class "Default")
      (node (ref "JP_MIXER_B") (pin "2") (pinfunction "2_2") (pintype "passive"))
    )
    (net (code "200") (name "unconnected-(OPAMP_SUM_STG-CMP-Pad5)") (class "Default")
      (node (ref "OPAMP_SUM_STG") (pin "5") (pinfunction "CMP_5") (pintype "passive"))
    )
    (net (code "201") (name "unconnected-(OPAMP_SUM_STG-ON-Pad1)") (class "Default")
      (node (ref "OPAMP_SUM_STG") (pin "1") (pinfunction "ON_1") (pintype "passive"))
    )
    (net (code "202") (name "unconnected-(OPAMP_SUM_STG-ON{slash}CMP-Pad8)") (class "Default")
      (node (ref "OPAMP_SUM_STG") (pin "8") (pinfunction "ON/CMP_8") (pintype "passive"))
    )
    (net (code "203") (name "unconnected-(STM32L432KC_CONN_A-NRST-Pad3.3)") (class "Default")
      (node (ref "STM32L432KC_CONN_") (pin "3.3") (pinfunction "NRST_3.3") (pintype "bidirectional"))
    )
    (net (code "204") (name "unconnected-(STM32L432KC_CONN_A-PB1-Pad3.9)") (class "Default")
      (node (ref "STM32L432KC_CONN_") (pin "3.9") (pinfunction "PB1_3.9") (pintype "bidirectional"))
    )
    (net (code "205") (name "unconnected-(STM32L432KC_CONN_A-PF0-Pad3.10)") (class "Default")
      (node (ref "STM32L432KC_CONN_") (pin "3.10") (pinfunction "PF0_3.10") (pintype "bidirectional"))
    )
    (net (code "206") (name "unconnected-(STM32L432KC_CONN_A-PF1-Pad3.11)") (class "Default")
      (node (ref "STM32L432KC_CONN_") (pin "3.11") (pinfunction "PF1_3.11") (pintype "bidirectional"))
    )
    (net (code "207") (name "unconnected-(STM32L432KC_CONN_B-+3V3-Pad4.14)") (class "Default")
      (node (ref "STM32L432KC_CONN_") (pin "4.14") (pinfunction "+3V3_4.14") (pintype "bidirectional"))
    )
    (net (code "208") (name "unconnected-(STM32L432KC_CONN_B-+5V-Pad4.4)") (class "Default")
      (node (ref "STM32L432KC_CONN_") (pin "4.4") (pinfunction "+5V_4.4") (pintype "bidirectional"))
    )
    (net (code "209") (name "unconnected-(STM32L432KC_CONN_B-AREF-Pad4.13)") (class "Default")
      (node (ref "STM32L432KC_CONN_") (pin "4.13") (pinfunction "AREF_4.13") (pintype "bidirectional"))
    )
    (net (code "210") (name "unconnected-(STM32L432KC_CONN_B-NRST-Pad4.3)") (class "Default")
      (node (ref "STM32L432KC_CONN_") (pin "4.3") (pinfunction "NRST_4.3") (pintype "bidirectional"))
    )
    (net (code "211") (name "unconnected-(STM32L432KC_CONN_B-PA0-Pad4.12)") (class "Default")
      (node (ref "STM32L432KC_CONN_") (pin "4.12") (pinfunction "PA0_4.12") (pintype "bidirectional"))
    )
    (net (code "212") (name "unconnected-(STM32L432KC_CONN_B-PA2-Pad4.5)") (class "Default")
      (node (ref "STM32L432KC_CONN_") (pin "4.5") (pinfunction "PA2_4.5") (pintype "bidirectional"))
    )
    (net (code "213") (name "unconnected-(STM32L432KC_CONN_B-PB3-Pad4.15)") (class "Default")
      (node (ref "STM32L432KC_CONN_") (pin "4.15") (pinfunction "PB3_4.15") (pintype "bidirectional"))
    )
    (net (code "214") (name "unconnected-(SUBBASS2-2CD-Pad4)") (class "Default")
      (node (ref "SUBBASS2") (pin "4") (pinfunction "2CD_4") (pintype "input"))
    )
    (net (code "215") (name "unconnected-(SUBBASS2-2CP-Pad3)") (class "Default")
      (node (ref "SUBBASS2") (pin "3") (pinfunction "2CP_3") (pintype "input"))
    )
    (net (code "216") (name "unconnected-(SUBBASS2-2J-Pad6)") (class "Default")
      (node (ref "SUBBASS2") (pin "6") (pinfunction "2J_6") (pintype "input"))
    )
    (net (code "217") (name "unconnected-(SUBBASS2-2K-Pad5)") (class "Default")
      (node (ref "SUBBASS2") (pin "5") (pinfunction "2K_5") (pintype "input"))
    )
    (net (code "218") (name "unconnected-(SUBBASS2-2Q-Pad1)") (class "Default")
      (node (ref "SUBBASS2") (pin "1") (pinfunction "2Q_1") (pintype "output"))
    )
    (net (code "219") (name "unconnected-(SUBBASS2-2SD-Pad7)") (class "Default")
      (node (ref "SUBBASS2") (pin "7") (pinfunction "2SD_7") (pintype "input"))
    )
    (net (code "220") (name "unconnected-(SUBBASS2-2~{Q}-Pad2)") (class "Default")
      (node (ref "SUBBASS2") (pin "2") (pinfunction "2~{Q}_2") (pintype "output"))
    )
    (net (code "221") (name "unconnected-(U1A-1_NC-Pad2)") (class "Default")
      (node (ref "U1") (pin "2") (pinfunction "1_NC_2") (pintype "passive"))
    )
    (net (code "222") (name "unconnected-(U1A-2_NC-Pad3)") (class "Default")
      (node (ref "U1") (pin "3") (pinfunction "2_NC_3") (pintype "passive"))
    )
    (net (code "223") (name "unconnected-(U1A-3_NC-Pad33)") (class "Default")
      (node (ref "U1") (pin "33") (pinfunction "3_NC_33") (pintype "passive"))
    )
    (net (code "224") (name "unconnected-(U1A-4_NC-Pad34)") (class "Default")
      (node (ref "U1") (pin "34") (pinfunction "4_NC_34") (pintype "passive"))
    )
    (net (code "225") (name "unconnected-(U1A-5_NC-Pad35)") (class "Default")
      (node (ref "U1") (pin "35") (pinfunction "5_NC_35") (pintype "passive"))
    )
    (net (code "226") (name "unconnected-(U1A-6_NC-Pad36)") (class "Default")
      (node (ref "U1") (pin "36") (pinfunction "6_NC_36") (pintype "passive"))
    )
    (net (code "227") (name "unconnected-(U1A-MON_IN1-Pad18)") (class "Default")
      (node (ref "U1") (pin "18") (pinfunction "MON_IN1_18") (pintype "input"))
    )
    (net (code "228") (name "unconnected-(U1A-MON_IN2-Pad19)") (class "Default")
      (node (ref "U1") (pin "19") (pinfunction "MON_IN2_19") (pintype "input"))
    )
    (net (code "229") (name "unconnected-(U1A-MON_OUT-Pad20)") (class "Default")
      (node (ref "U1") (pin "20") (pinfunction "MON_OUT_20") (pintype "tri_state"))
    )
    (net (code "230") (name "unconnected-(VCAC-I_DIODE-Pad2)") (class "Default")
      (node (ref "VCA") (pin "2") (pinfunction "I_DIODE_2") (pintype "input"))
    )
    (net (code "231") (name "unconnected-(VCO2C-I_DIODE-Pad2)") (class "Default")
      (node (ref "VCO2") (pin "2") (pinfunction "I_DIODE_2") (pintype "input"))
    )
    (net (code "232") (name "unconnected-(VCO2D-I_DIODE-Pad15)") (class "Default")
      (node (ref "VCO2") (pin "15") (pinfunction "I_DIODE_15") (pintype "input"))
    )
  )
)
